# tap_analog_elavult.net
KiCad netlist of a schematic drawn in EAGLE
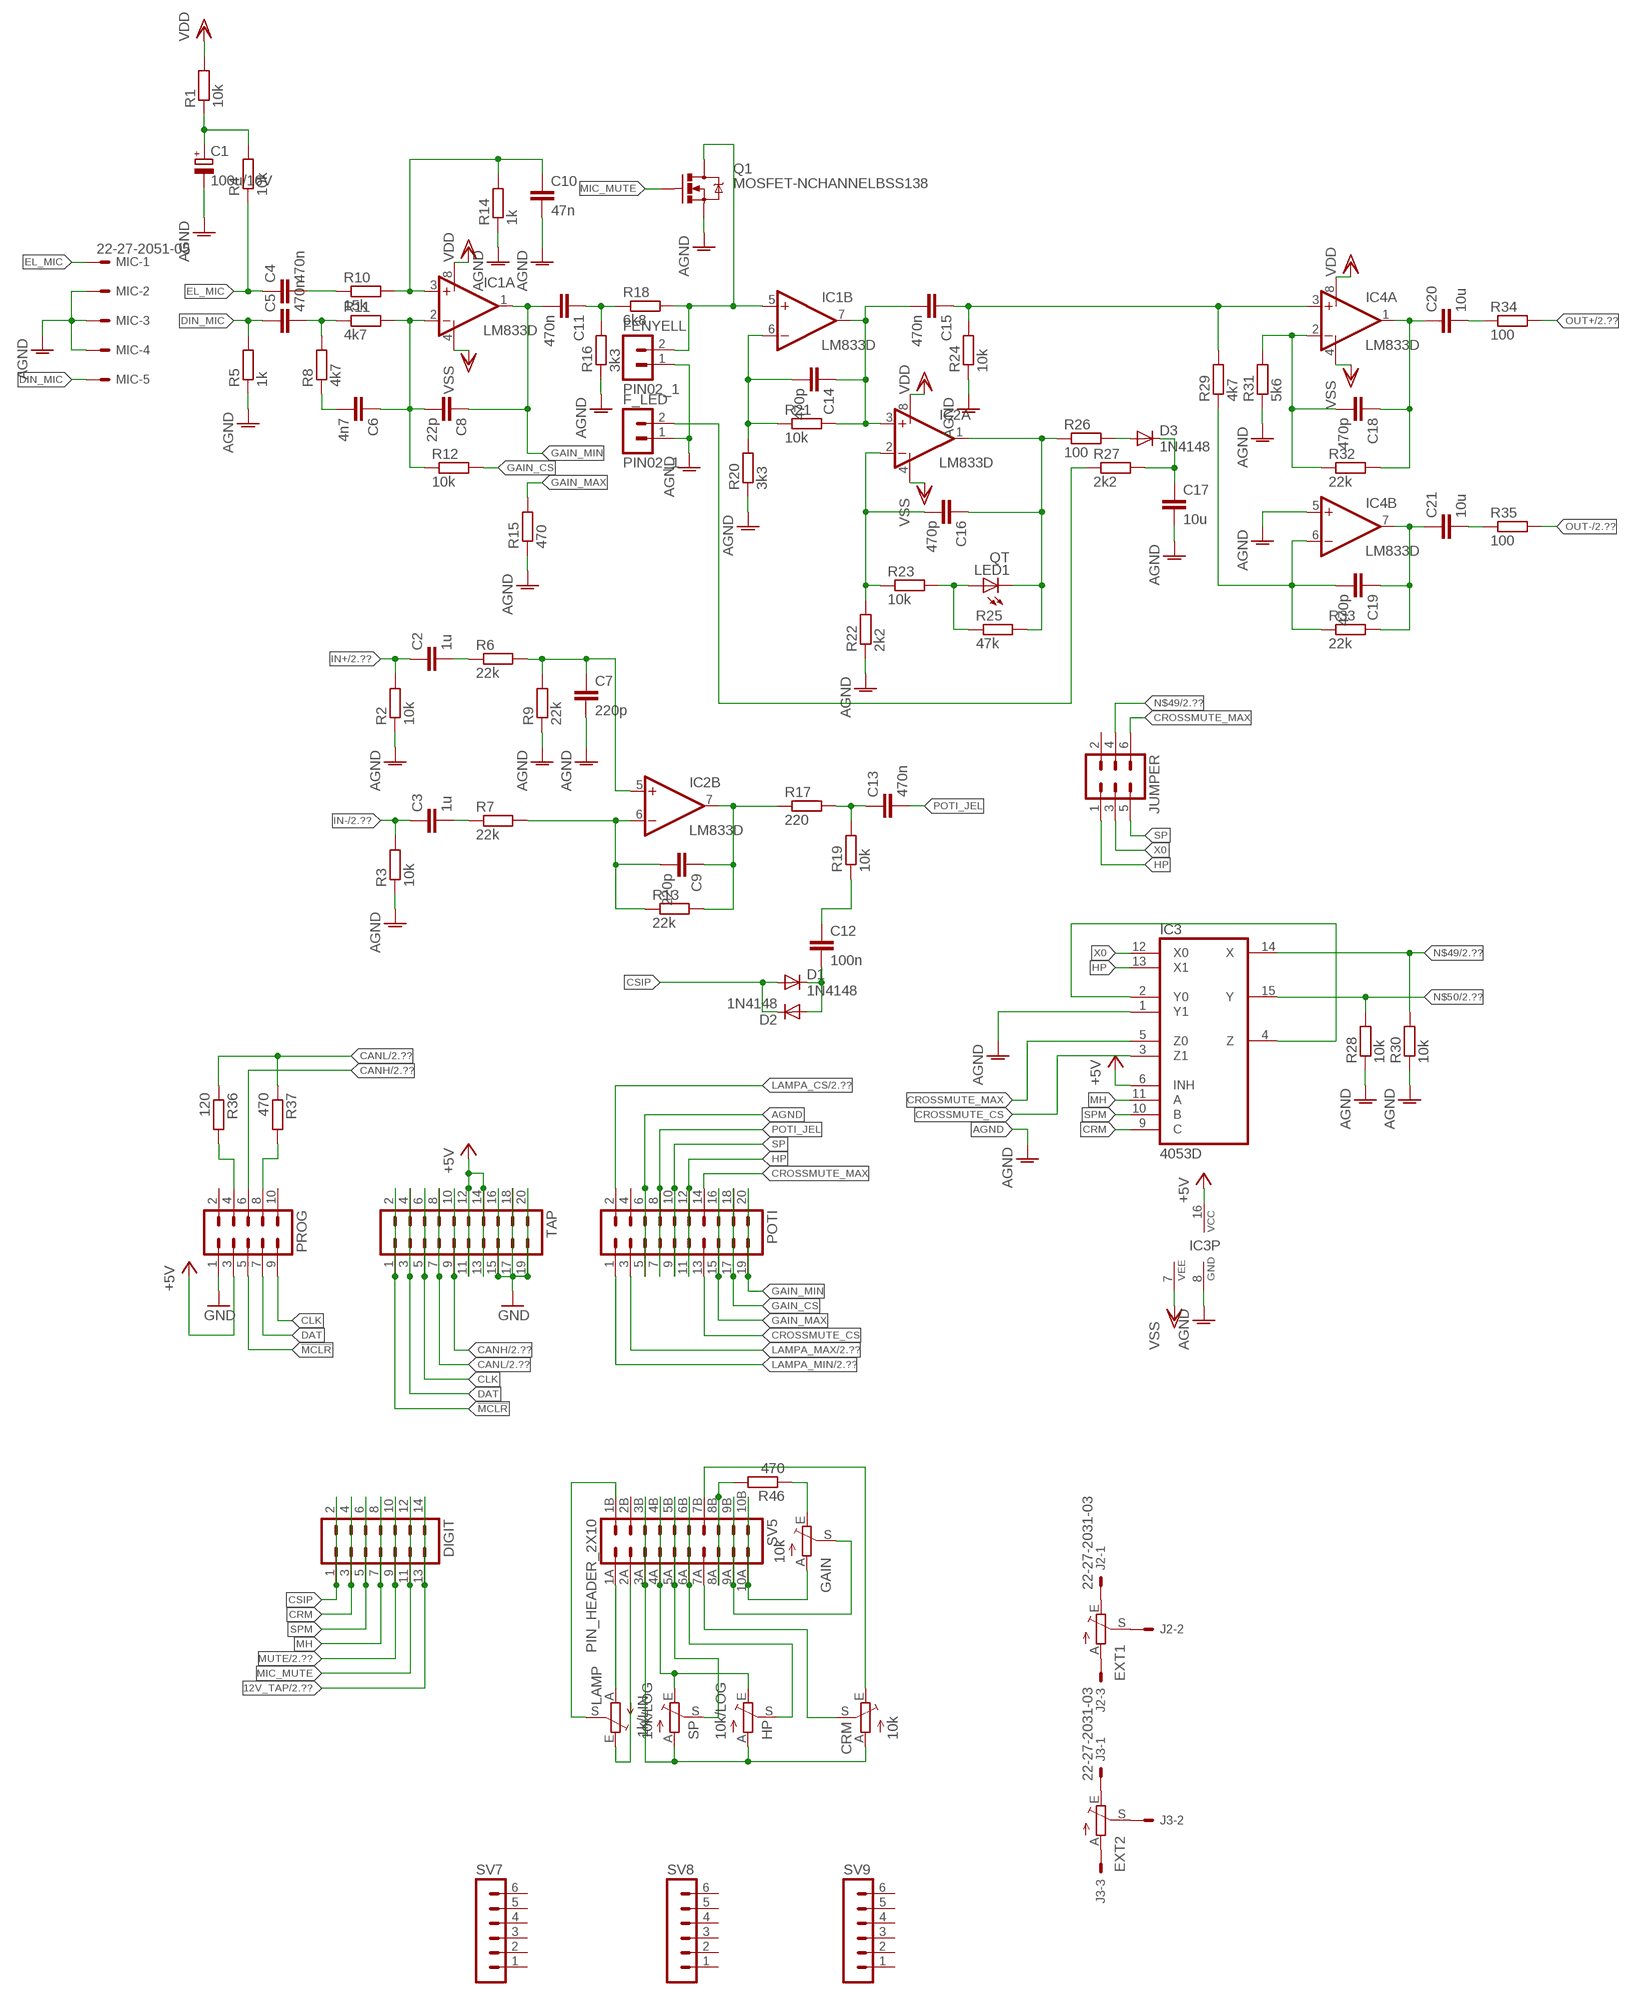
[diagram p0: schematic, sheet 1]
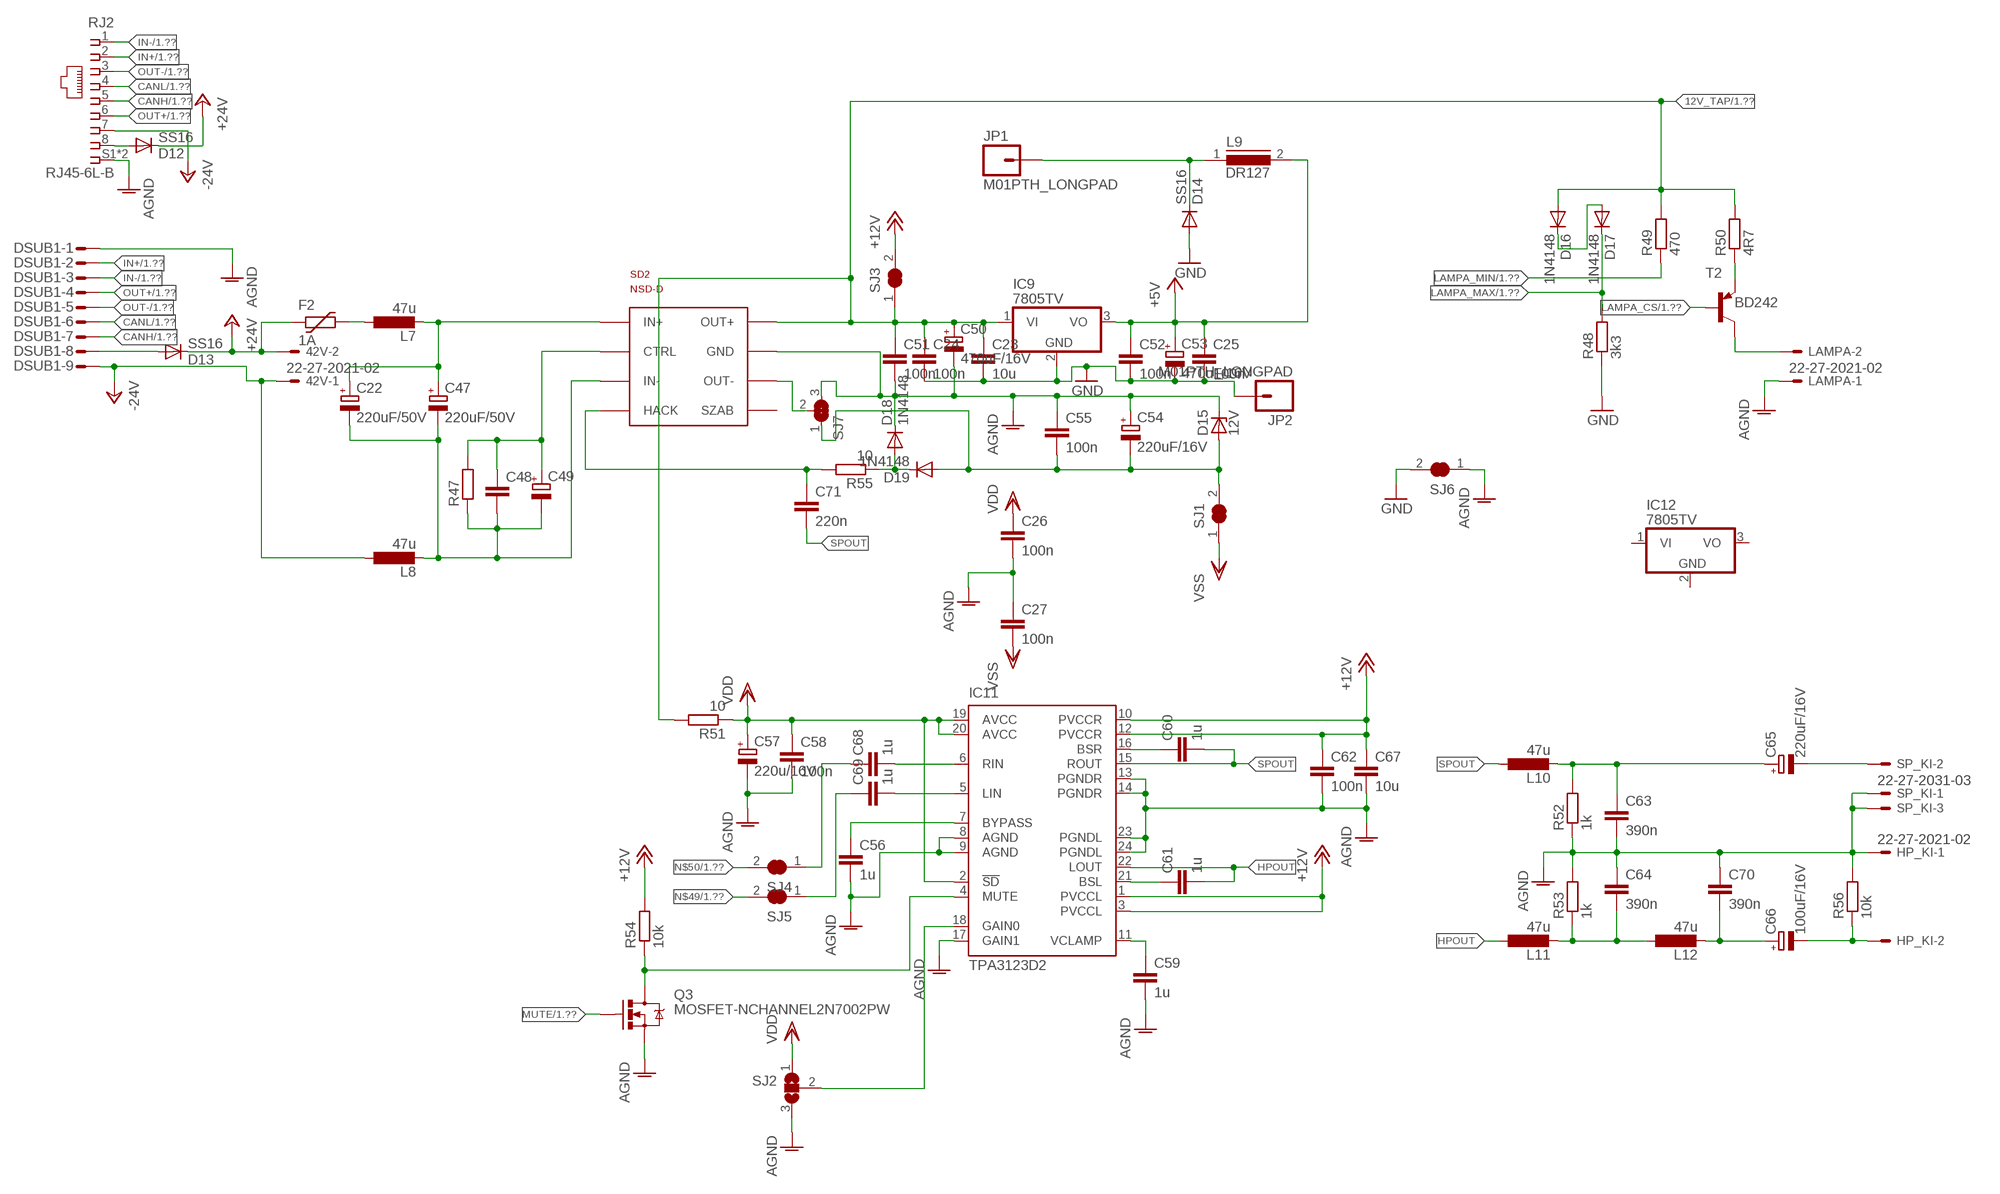
[diagram p1: schematic, sheet 2]

(export (version "E")
  (design (tool "Eeschema 10.0.6"))
  (components
    (comp (ref "42V")
      (value "22-27-2021-02")
      (footprint "eagle-import:6410-02")
      (libsource (lib "eagle-import") (part "22-?-0227-2021"))
    )
    (comp (ref "C22")
      (value "220uF/50V")
      (footprint "eagle-import:E3,5-8")
      (libsource (lib "eagle-import") (part "CPOL-EUE3.5-8"))
    )
    (comp (ref "C23")
      (value "10u")
      (footprint "eagle-import:C0805")
      (libsource (lib "eagle-import") (part "C-EUC0805"))
    )
    (comp (ref "C24")
      (value "100n")
      (footprint "eagle-import:C0805")
      (libsource (lib "eagle-import") (part "C-EUC0805"))
    )
    (comp (ref "C25")
      (value "100n")
      (footprint "eagle-import:C0805")
      (libsource (lib "eagle-import") (part "C-EUC0805"))
    )
    (comp (ref "C26")
      (value "100n")
      (footprint "eagle-import:C0805")
      (libsource (lib "eagle-import") (part "C-EUC0805"))
    )
    (comp (ref "C27")
      (value "100n")
      (footprint "eagle-import:C0805")
      (libsource (lib "eagle-import") (part "C-EUC0805"))
    )
    (comp (ref "C47")
      (value "220uF/50V")
      (footprint "eagle-import:E3,5-8")
      (libsource (lib "eagle-import") (part "CPOL-EUE3.5-8"))
    )
    (comp (ref "C48")
      (value "C-EUC0805")
      (footprint "eagle-import:C0805")
      (libsource (lib "eagle-import") (part "C-EUC0805"))
    )
    (comp (ref "C49")
      (value "CPOL-EUE2.5-5")
      (footprint "eagle-import:E2,5-5")
      (libsource (lib "eagle-import") (part "CPOL-EUE2.5-5"))
    )
    (comp (ref "C50")
      (value "470uF/16V")
      (footprint "eagle-import:E3,5-8")
      (libsource (lib "eagle-import") (part "CPOL-EUE3.5-8"))
    )
    (comp (ref "C51")
      (value "100n")
      (footprint "eagle-import:C0805")
      (libsource (lib "eagle-import") (part "C-EUC0805"))
    )
    (comp (ref "C52")
      (value "100n")
      (footprint "eagle-import:C0805")
      (libsource (lib "eagle-import") (part "C-EUC0805"))
    )
    (comp (ref "C53")
      (value "470uF/16V")
      (footprint "eagle-import:E3,5-8")
      (libsource (lib "eagle-import") (part "CPOL-EUE3.5-8"))
    )
    (comp (ref "C54")
      (value "220uF/16V")
      (footprint "eagle-import:E2,5-6")
      (libsource (lib "eagle-import") (part "CPOL-EUE2.5-6"))
    )
    (comp (ref "C55")
      (value "100n")
      (footprint "eagle-import:C0805")
      (libsource (lib "eagle-import") (part "C-EUC0805"))
    )
    (comp (ref "C56")
      (value "1u")
      (footprint "eagle-import:C0805")
      (libsource (lib "eagle-import") (part "C-EUC0805"))
    )
    (comp (ref "C57")
      (value "220u/16V")
      (footprint "eagle-import:E2,5-6")
      (libsource (lib "eagle-import") (part "CPOL-EUE2.5-6"))
    )
    (comp (ref "C58")
      (value "100n")
      (footprint "eagle-import:C0805")
      (libsource (lib "eagle-import") (part "C-EUC0805"))
    )
    (comp (ref "C59")
      (value "1u")
      (footprint "eagle-import:C0805")
      (libsource (lib "eagle-import") (part "C-EUC0805"))
    )
    (comp (ref "C60")
      (value "1u")
      (footprint "eagle-import:C0805")
      (libsource (lib "eagle-import") (part "C-EUC0805"))
    )
    (comp (ref "C61")
      (value "1u")
      (footprint "eagle-import:C0805")
      (libsource (lib "eagle-import") (part "C-EUC0805"))
    )
    (comp (ref "C62")
      (value "100n")
      (footprint "eagle-import:C0805")
      (libsource (lib "eagle-import") (part "C-EUC0805"))
    )
    (comp (ref "C63")
      (value "390n")
      (footprint "eagle-import:C0805")
      (libsource (lib "eagle-import") (part "C-EUC0805"))
    )
    (comp (ref "C64")
      (value "390n")
      (footprint "eagle-import:C0805")
      (libsource (lib "eagle-import") (part "C-EUC0805"))
    )
    (comp (ref "C65")
      (value "220uF/16V")
      (footprint "eagle-import:E2,5-6")
      (libsource (lib "eagle-import") (part "CPOL-EUE2.5-6"))
    )
    (comp (ref "C66")
      (value "100uF/16V")
      (footprint "eagle-import:E2,5-5")
      (libsource (lib "eagle-import") (part "CPOL-EUE2.5-5"))
    )
    (comp (ref "C67")
      (value "10u")
      (footprint "eagle-import:C0805")
      (libsource (lib "eagle-import") (part "C-EUC0805"))
    )
    (comp (ref "C68")
      (value "1u")
      (footprint "eagle-import:C0805")
      (libsource (lib "eagle-import") (part "C-EUC0805"))
    )
    (comp (ref "C69")
      (value "1u")
      (footprint "eagle-import:C0805")
      (libsource (lib "eagle-import") (part "C-EUC0805"))
    )
    (comp (ref "C70")
      (value "390n")
      (footprint "eagle-import:C0805")
      (libsource (lib "eagle-import") (part "C-EUC0805"))
    )
    (comp (ref "C71")
      (value "220n")
      (footprint "eagle-import:C0805")
      (libsource (lib "eagle-import") (part "C-EUC0805"))
    )
    (comp (ref "D12")
      (value "SS16")
      (footprint "eagle-import:DO-214AC")
      (libsource (lib "eagle-import") (part "dp_devices_DIODE-DO-214AC"))
    )
    (comp (ref "D13")
      (value "SS16")
      (footprint "eagle-import:DO-214AC")
      (libsource (lib "eagle-import") (part "dp_devices_DIODE-DO-214AC"))
    )
    (comp (ref "D14")
      (value "SS16")
      (footprint "eagle-import:DO-214AC")
      (libsource (lib "eagle-import") (part "dp_devices_DIODE-DO-214AC"))
    )
    (comp (ref "D15")
      (value "12V")
      (footprint "eagle-import:SOD80C")
      (libsource (lib "eagle-import") (part "ZENER-DIODESOD80C"))
    )
    (comp (ref "D16")
      (value "1N4148")
      (footprint "eagle-import:SOD80C")
      (libsource (lib "eagle-import") (part "DIODE-SOD80C"))
    )
    (comp (ref "D17")
      (value "1N4148")
      (footprint "eagle-import:SOD80C")
      (libsource (lib "eagle-import") (part "DIODE-SOD80C"))
    )
    (comp (ref "D18")
      (value "1N4148")
      (footprint "eagle-import:SOD80C")
      (libsource (lib "eagle-import") (part "DIODE-SOD80C"))
    )
    (comp (ref "D19")
      (value "1N4148")
      (footprint "eagle-import:SOD80C")
      (libsource (lib "eagle-import") (part "DIODE-SOD80C"))
    )
    (comp (ref "DSUB1")
      (value "M09-182S")
      (footprint "eagle-import:182-009-MALE")
      (libsource (lib "eagle-import") (part "M09?S-182"))
    )
    (comp (ref "F2")
      (value "1A")
      (footprint "eagle-import:PTC1812L")
      (libsource (lib "eagle-import") (part "FUSE_PTC-1812"))
    )
    (comp (ref "HP_KI")
      (value "22-27-2021-02")
      (footprint "eagle-import:6410-02")
      (libsource (lib "eagle-import") (part "22-?-0227-2021"))
    )
    (comp (ref "IC9")
      (value "7805TV")
      (footprint "eagle-import:TO220V")
      (libsource (lib "eagle-import") (part "78TV05"))
    )
    (comp (ref "IC11")
      (value "TPA3123D2")
      (footprint "eagle-import:PWP-TSSOP24")
      (fields (field (name "MPN") "TPA3123D2PWP"))
      (libsource (lib "eagle-import") (part "TPA3123D2"))
    )
    (comp (ref "IC12")
      (value "7805TV")
      (footprint "eagle-import:TO220V")
      (libsource (lib "eagle-import") (part "78TV05"))
    )
    (comp (ref "JP1")
      (value "M01PTH_LONGPAD")
      (footprint "eagle-import:1X01_LONGPAD")
      (libsource (lib "eagle-import") (part "M01PTH_LONGPAD"))
    )
    (comp (ref "JP2")
      (value "M01PTH_LONGPAD")
      (footprint "eagle-import:1X01_LONGPAD")
      (libsource (lib "eagle-import") (part "M01PTH_LONGPAD"))
    )
    (comp (ref "L7")
      (value "47u")
      (footprint "eagle-import:PIS2816")
      (libsource (lib "eagle-import") (part "L-EUPIS2816"))
    )
    (comp (ref "L8")
      (value "47u")
      (footprint "eagle-import:PIS2816")
      (libsource (lib "eagle-import") (part "L-EUPIS2816"))
    )
    (comp (ref "L9")
      (value "DR127")
      (footprint "eagle-import:DR127")
      (libsource (lib "eagle-import") (part "DR127"))
    )
    (comp (ref "L10")
      (value "47u")
      (footprint "eagle-import:PIS2816")
      (libsource (lib "eagle-import") (part "L-EUPIS2816"))
    )
    (comp (ref "L11")
      (value "47u")
      (footprint "eagle-import:PIS2816")
      (libsource (lib "eagle-import") (part "L-EUPIS2816"))
    )
    (comp (ref "L12")
      (value "47u")
      (footprint "eagle-import:PIS2816")
      (libsource (lib "eagle-import") (part "L-EUPIS2816"))
    )
    (comp (ref "LAMPA")
      (value "22-27-2021-02")
      (footprint "eagle-import:6410-02")
      (libsource (lib "eagle-import") (part "22-?-0227-2021"))
    )
    (comp (ref "Q3")
      (value "MOSFET-NCHANNEL2N7002PW")
      (footprint "eagle-import:SOT323")
      (libsource (lib "eagle-import") (part "MOSFET-NCHANNEL2N7002PW"))
    )
    (comp (ref "R47")
      (value "R-EU_R0805")
      (footprint "eagle-import:R0805")
      (libsource (lib "eagle-import") (part "R-EU_R0805"))
    )
    (comp (ref "R48")
      (value "3k3")
      (footprint "eagle-import:R0805")
      (libsource (lib "eagle-import") (part "R-EU_R0805"))
    )
    (comp (ref "R49")
      (value "470")
      (footprint "eagle-import:R0805")
      (libsource (lib "eagle-import") (part "R-EU_R0805"))
    )
    (comp (ref "R50")
      (value "4R7")
      (footprint "eagle-import:R0805")
      (libsource (lib "eagle-import") (part "R-EU_R0805"))
    )
    (comp (ref "R51")
      (value "10")
      (footprint "eagle-import:R1210")
      (libsource (lib "eagle-import") (part "R-EU_R1210"))
    )
    (comp (ref "R52")
      (value "1k")
      (footprint "eagle-import:R0805")
      (libsource (lib "eagle-import") (part "R-EU_R0805"))
    )
    (comp (ref "R53")
      (value "1k")
      (footprint "eagle-import:R0805")
      (libsource (lib "eagle-import") (part "R-EU_R0805"))
    )
    (comp (ref "R54")
      (value "10k")
      (footprint "eagle-import:R0805")
      (libsource (lib "eagle-import") (part "R-EU_R0805"))
    )
    (comp (ref "R55")
      (value "10")
      (footprint "eagle-import:R0805")
      (libsource (lib "eagle-import") (part "R-EU_R0805"))
    )
    (comp (ref "R56")
      (value "10k")
      (footprint "eagle-import:R0805")
      (libsource (lib "eagle-import") (part "R-EU_R0805"))
    )
    (comp (ref "RJ2")
      (value "RJ45-6L-B")
      (footprint "eagle-import:RJ45")
      (libsource (lib "eagle-import") (part "RJ45-6L-B"))
    )
    (comp (ref "SD2")
      (value "NSD-D")
      (footprint "eagle-import:NSD-D")
      (libsource (lib "eagle-import") (part "NSD-D"))
    )
    (comp (ref "SJ1")
      (value "SOLDERJUMPER_CLOSED")
      (footprint "eagle-import:SOLDERJUMPER_CLOSEDWIRE")
      (libsource (lib "eagle-import") (part "SOLDERJUMPER_CLOSED"))
    )
    (comp (ref "SJ2")
      (value "SJ2W")
      (footprint "eagle-import:SJ_2")
      (libsource (lib "eagle-import") (part "SJ2W"))
    )
    (comp (ref "SJ3")
      (value "SOLDERJUMPER_CLOSED")
      (footprint "eagle-import:SOLDERJUMPER_CLOSEDWIRE")
      (libsource (lib "eagle-import") (part "SOLDERJUMPER_CLOSED"))
    )
    (comp (ref "SJ4")
      (value "SOLDERJUMPER_CLOSED")
      (footprint "eagle-import:SOLDERJUMPER_CLOSEDWIRE")
      (libsource (lib "eagle-import") (part "SOLDERJUMPER_CLOSED"))
    )
    (comp (ref "SJ5")
      (value "SOLDERJUMPER_CLOSED")
      (footprint "eagle-import:SOLDERJUMPER_CLOSEDWIRE")
      (libsource (lib "eagle-import") (part "SOLDERJUMPER_CLOSED"))
    )
    (comp (ref "SJ6")
      (value "SOLDERJUMPER_CLOSED")
      (footprint "eagle-import:SOLDERJUMPER_CLOSEDWIRE")
      (libsource (lib "eagle-import") (part "SOLDERJUMPER_CLOSED"))
    )
    (comp (ref "SJ7")
      (value "SOLDERJUMPER_2WAY")
      (footprint "eagle-import:SOLDERJUMPER_2WAY_OPEN_NOPASTE")
      (libsource (lib "eagle-import") (part "SOLDERJUMPER_2WAY"))
    )
    (comp (ref "SP_KI")
      (value "22-27-2031-03")
      (footprint "eagle-import:6410-03")
      (libsource (lib "eagle-import") (part "22-?-0327-2031"))
    )
    (comp (ref "T2")
      (value "BD242")
      (footprint "eagle-import:TO220V")
      (libsource (lib "eagle-import") (part "-PNP-TO220V"))
    )
    (comp (ref "C1")
      (value "100u/16V")
      (footprint "eagle-import:E2,5-5")
      (libsource (lib "eagle-import") (part "CPOL-EUE2.5-5"))
    )
    (comp (ref "C2")
      (value "1u")
      (footprint "eagle-import:C0805")
      (libsource (lib "eagle-import") (part "C-EUC0805"))
    )
    (comp (ref "C3")
      (value "1u")
      (footprint "eagle-import:C0805")
      (libsource (lib "eagle-import") (part "C-EUC0805"))
    )
    (comp (ref "C4")
      (value "470n")
      (footprint "eagle-import:C0805")
      (libsource (lib "eagle-import") (part "C-EUC0805"))
    )
    (comp (ref "C5")
      (value "470n")
      (footprint "eagle-import:C0805")
      (libsource (lib "eagle-import") (part "C-EUC0805"))
    )
    (comp (ref "C6")
      (value "4n7")
      (footprint "eagle-import:C0805")
      (libsource (lib "eagle-import") (part "C-EUC0805"))
    )
    (comp (ref "C7")
      (value "220p")
      (footprint "eagle-import:C0805")
      (libsource (lib "eagle-import") (part "C-EUC0805"))
    )
    (comp (ref "C8")
      (value "22p")
      (footprint "eagle-import:C0805")
      (libsource (lib "eagle-import") (part "C-EUC0805"))
    )
    (comp (ref "C9")
      (value "220p")
      (footprint "eagle-import:C0805")
      (libsource (lib "eagle-import") (part "C-EUC0805"))
    )
    (comp (ref "C10")
      (value "47n")
      (footprint "eagle-import:C0805")
      (libsource (lib "eagle-import") (part "C-EUC0805"))
    )
    (comp (ref "C11")
      (value "470n")
      (footprint "eagle-import:C0805")
      (libsource (lib "eagle-import") (part "C-EUC0805"))
    )
    (comp (ref "C12")
      (value "100n")
      (footprint "eagle-import:C0805")
      (libsource (lib "eagle-import") (part "C-EUC0805"))
    )
    (comp (ref "C13")
      (value "470n")
      (footprint "eagle-import:C0805")
      (libsource (lib "eagle-import") (part "C-EUC0805"))
    )
    (comp (ref "C14")
      (value "470p")
      (footprint "eagle-import:C0805")
      (libsource (lib "eagle-import") (part "C-EUC0805"))
    )
    (comp (ref "C15")
      (value "470n")
      (footprint "eagle-import:C0805")
      (libsource (lib "eagle-import") (part "C-EUC0805"))
    )
    (comp (ref "C16")
      (value "470p")
      (footprint "eagle-import:C0805")
      (libsource (lib "eagle-import") (part "C-EUC0805"))
    )
    (comp (ref "C17")
      (value "10u")
      (footprint "eagle-import:C0805")
      (libsource (lib "eagle-import") (part "C-EUC0805"))
    )
    (comp (ref "C18")
      (value "470p")
      (footprint "eagle-import:C0805")
      (libsource (lib "eagle-import") (part "C-EUC0805"))
    )
    (comp (ref "C19")
      (value "470p")
      (footprint "eagle-import:C0805")
      (libsource (lib "eagle-import") (part "C-EUC0805"))
    )
    (comp (ref "C20")
      (value "10u")
      (footprint "eagle-import:C0805")
      (libsource (lib "eagle-import") (part "C-EUC0805"))
    )
    (comp (ref "C21")
      (value "10u")
      (footprint "eagle-import:C0805")
      (libsource (lib "eagle-import") (part "C-EUC0805"))
    )
    (comp (ref "CRM")
      (value "10k")
      (footprint "eagle-import:PT-10")
      (libsource (lib "eagle-import") (part "TRIM_EU-PT10"))
    )
    (comp (ref "D1")
      (value "1N4148")
      (footprint "eagle-import:SOD80C")
      (libsource (lib "eagle-import") (part "DIODE-SOD80C"))
    )
    (comp (ref "D2")
      (value "1N4148")
      (footprint "eagle-import:SOD80C")
      (libsource (lib "eagle-import") (part "DIODE-SOD80C"))
    )
    (comp (ref "D3")
      (value "1N4148")
      (footprint "eagle-import:SOD80C")
      (libsource (lib "eagle-import") (part "DIODE-SOD80C"))
    )
    (comp (ref "DIGIT")
      (value "MA07-2")
      (footprint "eagle-import:MA07-2")
      (libsource (lib "eagle-import") (part "MA07-2"))
    )
    (comp (ref "EXT1")
      (value "TRIM_EU-PT10")
      (footprint "eagle-import:PT-10")
      (libsource (lib "eagle-import") (part "TRIM_EU-PT10"))
    )
    (comp (ref "EXT2")
      (value "TRIM_EU-PT10")
      (footprint "eagle-import:PT-10")
      (libsource (lib "eagle-import") (part "TRIM_EU-PT10"))
    )
    (comp (ref "FENYELL")
      (value "PIN02_1")
      (footprint "eagle-import:PIN02_1")
      (libsource (lib "eagle-import") (part "PIN02_1"))
    )
    (comp (ref "F_LED")
      (value "PIN02_1")
      (footprint "eagle-import:PIN02_1")
      (libsource (lib "eagle-import") (part "PIN02_1"))
    )
    (comp (ref "GAIN")
      (value "10k")
      (footprint "eagle-import:PT-10")
      (libsource (lib "eagle-import") (part "TRIM_EU-PT10"))
    )
    (comp (ref "HP")
      (value "10k/LOG")
      (footprint "eagle-import:POT_NAR")
      (libsource (lib "eagle-import") (part "TRIM_EU-POT_WHOLE"))
    )
    (comp (ref "IC1")
      (value "LM833D")
      (footprint "eagle-import:SO08")
      (libsource (lib "eagle-import") (part "LM833D"))
    )
    (comp (ref "IC2")
      (value "LM833D")
      (footprint "eagle-import:SO08")
      (libsource (lib "eagle-import") (part "LM833D"))
    )
    (comp (ref "IC3")
      (value "4053D")
      (footprint "eagle-import:SO16")
      (libsource (lib "eagle-import") (part "4053D"))
    )
    (comp (ref "IC4")
      (value "LM833D")
      (footprint "eagle-import:SO08")
      (libsource (lib "eagle-import") (part "LM833D"))
    )
    (comp (ref "J2")
      (value "22-27-2031-03")
      (footprint "eagle-import:6410-03")
      (libsource (lib "eagle-import") (part "22-?-0327-2031"))
    )
    (comp (ref "J3")
      (value "22-27-2031-03")
      (footprint "eagle-import:6410-03")
      (libsource (lib "eagle-import") (part "22-?-0327-2031"))
    )
    (comp (ref "JUMPER")
      (value "MA03-2")
      (footprint "eagle-import:MA03-2")
      (libsource (lib "eagle-import") (part "MA03-2"))
    )
    (comp (ref "LAMP")
      (value "1k/LIN")
      (footprint "eagle-import:POT_NAR")
      (libsource (lib "eagle-import") (part "TRIM_EU-POT_WHOLE"))
    )
    (comp (ref "LED1")
      (value "QT")
      (footprint "eagle-import:LED3MM")
      (libsource (lib "eagle-import") (part "LED3MM"))
    )
    (comp (ref "MIC")
      (value "22-27-2051-05")
      (footprint "eagle-import:6410-05")
      (libsource (lib "eagle-import") (part "22-?-0527-2051"))
    )
    (comp (ref "POTI")
      (value "MA10-2")
      (footprint "eagle-import:MA10-2")
      (libsource (lib "eagle-import") (part "MA10-2"))
    )
    (comp (ref "PROG")
      (value "ML10L")
      (footprint "eagle-import:ML10L")
      (libsource (lib "eagle-import") (part "ML10L"))
    )
    (comp (ref "Q1")
      (value "MOSFET-NCHANNELBSS138")
      (footprint "eagle-import:SOT23")
      (libsource (lib "eagle-import") (part "MOSFET-NCHANNELBSS138"))
    )
    (comp (ref "R1")
      (value "10k")
      (footprint "eagle-import:R0805")
      (libsource (lib "eagle-import") (part "R-EU_R0805"))
    )
    (comp (ref "R2")
      (value "10k")
      (footprint "eagle-import:R0805")
      (libsource (lib "eagle-import") (part "R-EU_R0805"))
    )
    (comp (ref "R3")
      (value "10k")
      (footprint "eagle-import:R0805")
      (libsource (lib "eagle-import") (part "R-EU_R0805"))
    )
    (comp (ref "R4")
      (value "10k")
      (footprint "eagle-import:R0805")
      (libsource (lib "eagle-import") (part "R-EU_R0805"))
    )
    (comp (ref "R5")
      (value "1k")
      (footprint "eagle-import:R0805")
      (libsource (lib "eagle-import") (part "R-EU_R0805"))
    )
    (comp (ref "R6")
      (value "22k")
      (footprint "eagle-import:R0805")
      (libsource (lib "eagle-import") (part "R-EU_R0805"))
    )
    (comp (ref "R7")
      (value "22k")
      (footprint "eagle-import:R0805")
      (libsource (lib "eagle-import") (part "R-EU_R0805"))
    )
    (comp (ref "R8")
      (value "4k7")
      (footprint "eagle-import:R0805")
      (libsource (lib "eagle-import") (part "R-EU_R0805"))
    )
    (comp (ref "R9")
      (value "22k")
      (footprint "eagle-import:R0805")
      (libsource (lib "eagle-import") (part "R-EU_R0805"))
    )
    (comp (ref "R10")
      (value "15k")
      (footprint "eagle-import:R0805")
      (libsource (lib "eagle-import") (part "R-EU_R0805"))
    )
    (comp (ref "R11")
      (value "4k7")
      (footprint "eagle-import:R0805")
      (libsource (lib "eagle-import") (part "R-EU_R0805"))
    )
    (comp (ref "R12")
      (value "10k")
      (footprint "eagle-import:R0805")
      (libsource (lib "eagle-import") (part "R-EU_R0805"))
    )
    (comp (ref "R13")
      (value "22k")
      (footprint "eagle-import:R0805")
      (libsource (lib "eagle-import") (part "R-EU_R0805"))
    )
    (comp (ref "R14")
      (value "1k")
      (footprint "eagle-import:R0805")
      (libsource (lib "eagle-import") (part "R-EU_R0805"))
    )
    (comp (ref "R15")
      (value "470")
      (footprint "eagle-import:R0805")
      (libsource (lib "eagle-import") (part "R-EU_R0805"))
    )
    (comp (ref "R16")
      (value "3k3")
      (footprint "eagle-import:R0805")
      (libsource (lib "eagle-import") (part "R-EU_R0805"))
    )
    (comp (ref "R17")
      (value "220")
      (footprint "eagle-import:R0805")
      (libsource (lib "eagle-import") (part "R-EU_R0805"))
    )
    (comp (ref "R18")
      (value "6k8")
      (footprint "eagle-import:R0805")
      (libsource (lib "eagle-import") (part "R-EU_R0805"))
    )
    (comp (ref "R19")
      (value "10k")
      (footprint "eagle-import:R0805")
      (libsource (lib "eagle-import") (part "R-EU_R0805"))
    )
    (comp (ref "R20")
      (value "3k3")
      (footprint "eagle-import:R0805")
      (libsource (lib "eagle-import") (part "R-EU_R0805"))
    )
    (comp (ref "R21")
      (value "10k")
      (footprint "eagle-import:R0805")
      (libsource (lib "eagle-import") (part "R-EU_R0805"))
    )
    (comp (ref "R22")
      (value "2k2")
      (footprint "eagle-import:R0805")
      (libsource (lib "eagle-import") (part "R-EU_R0805"))
    )
    (comp (ref "R23")
      (value "10k")
      (footprint "eagle-import:R0805")
      (libsource (lib "eagle-import") (part "R-EU_R0805"))
    )
    (comp (ref "R24")
      (value "10k")
      (footprint "eagle-import:R0805")
      (libsource (lib "eagle-import") (part "R-EU_R0805"))
    )
    (comp (ref "R25")
      (value "47k")
      (footprint "eagle-import:R0805")
      (libsource (lib "eagle-import") (part "R-EU_R0805"))
    )
    (comp (ref "R26")
      (value "100")
      (footprint "eagle-import:R0805")
      (libsource (lib "eagle-import") (part "R-EU_R0805"))
    )
    (comp (ref "R27")
      (value "2k2")
      (footprint "eagle-import:R0805")
      (libsource (lib "eagle-import") (part "R-EU_R0805"))
    )
    (comp (ref "R28")
      (value "10k")
      (footprint "eagle-import:R0805")
      (libsource (lib "eagle-import") (part "R-EU_R0805"))
    )
    (comp (ref "R29")
      (value "4k7")
      (footprint "eagle-import:R0805")
      (libsource (lib "eagle-import") (part "R-EU_R0805"))
    )
    (comp (ref "R30")
      (value "10k")
      (footprint "eagle-import:R0805")
      (libsource (lib "eagle-import") (part "R-EU_R0805"))
    )
    (comp (ref "R31")
      (value "5k6")
      (footprint "eagle-import:R0805")
      (libsource (lib "eagle-import") (part "R-EU_R0805"))
    )
    (comp (ref "R32")
      (value "22k")
      (footprint "eagle-import:R0805")
      (libsource (lib "eagle-import") (part "R-EU_R0805"))
    )
    (comp (ref "R33")
      (value "22k")
      (footprint "eagle-import:R0805")
      (libsource (lib "eagle-import") (part "R-EU_R0805"))
    )
    (comp (ref "R34")
      (value "100")
      (footprint "eagle-import:R0805")
      (libsource (lib "eagle-import") (part "R-EU_R0805"))
    )
    (comp (ref "R35")
      (value "100")
      (footprint "eagle-import:R0805")
      (libsource (lib "eagle-import") (part "R-EU_R0805"))
    )
    (comp (ref "R36")
      (value "120")
      (footprint "eagle-import:R0805")
      (libsource (lib "eagle-import") (part "R-EU_R0805"))
    )
    (comp (ref "R37")
      (value "470")
      (footprint "eagle-import:R0805")
      (libsource (lib "eagle-import") (part "R-EU_R0805"))
    )
    (comp (ref "R46")
      (value "470")
      (footprint "eagle-import:R0805")
      (libsource (lib "eagle-import") (part "R-EU_R0805"))
    )
    (comp (ref "SP")
      (value "10k/LOG")
      (footprint "eagle-import:POT_NAR")
      (libsource (lib "eagle-import") (part "TRIM_EU-POT_WHOLE"))
    )
    (comp (ref "SV5")
      (value "PIN_HEADER_2X10")
      (footprint "eagle-import:PIN_HEADER_2X10SMD")
      (libsource (lib "eagle-import") (part "PIN_HEADER_2X10"))
    )
    (comp (ref "SV7")
      (value "MA06-1")
      (footprint "eagle-import:MA06-1")
      (libsource (lib "eagle-import") (part "MA06-1"))
    )
    (comp (ref "SV8")
      (value "MA06-1")
      (footprint "eagle-import:MA06-1")
      (libsource (lib "eagle-import") (part "MA06-1"))
    )
    (comp (ref "SV9")
      (value "MA06-1")
      (footprint "eagle-import:MA06-1")
      (libsource (lib "eagle-import") (part "MA06-1"))
    )
    (comp (ref "TAP")
      (value "MA10-2")
      (footprint "eagle-import:MA10-2")
      (libsource (lib "eagle-import") (part "MA10-2"))
    )
  )
  (nets
    (net (code "1") (name "+5V") (class "Default")
      (node (ref "C25") (pin "1") (pinfunction "1_1") (pintype "passive"))
      (node (ref "C52") (pin "1") (pinfunction "1_1") (pintype "passive"))
      (node (ref "C53") (pin "+") (pinfunction "+_+") (pintype "passive"))
      (node (ref "IC3") (pin "16") (pinfunction "VCC_16") (pintype "power_in"))
      (node (ref "IC3") (pin "6") (pinfunction "INH_6") (pintype "input"))
      (node (ref "IC9") (pin "3") (pinfunction "VO_3") (pintype "passive"))
      (node (ref "L9") (pin "2") (pinfunction "2_2") (pintype "passive"))
      (node (ref "PROG") (pin "3") (pinfunction "3_3") (pintype "passive"))
      (node (ref "TAP") (pin "11") (pinfunction "11_11") (pintype "passive"))
      (node (ref "TAP") (pin "12") (pinfunction "12_12") (pintype "passive"))
      (node (ref "TAP") (pin "13") (pinfunction "13_13") (pintype "passive"))
      (node (ref "TAP") (pin "14") (pinfunction "14_14") (pintype "passive"))
    )
    (net (code "2") (name "+12V") (class "Default")
      (node (ref "C62") (pin "1") (pinfunction "1_1") (pintype "passive"))
      (node (ref "C67") (pin "1") (pinfunction "1_1") (pintype "passive"))
      (node (ref "IC11") (pin "1") (pinfunction "PVCCL_1") (pintype "input"))
      (node (ref "IC11") (pin "10") (pinfunction "PVCCR_10") (pintype "input"))
      (node (ref "IC11") (pin "12") (pinfunction "PVCCR_12") (pintype "input"))
      (node (ref "IC11") (pin "3") (pinfunction "PVCCL_3") (pintype "input"))
      (node (ref "R54") (pin "2") (pinfunction "2_2") (pintype "passive"))
      (node (ref "SJ3") (pin "2") (pinfunction "2_2") (pintype "passive"))
    )
    (net (code "3") (name "+24V") (class "Default")
      (node (ref "42V") (pin "2") (pinfunction "S_2") (pintype "passive"))
      (node (ref "D12") (pin "1") (pinfunction "C_1") (pintype "passive"))
      (node (ref "D13") (pin "1") (pinfunction "C_1") (pintype "passive"))
      (node (ref "F2") (pin "1") (pinfunction "1_1") (pintype "passive"))
    )
    (net (code "4") (name "-24V") (class "Default")
      (node (ref "42V") (pin "1") (pinfunction "S_1") (pintype "passive"))
      (node (ref "DSUB1") (pin "9") (pinfunction "M_9") (pintype "passive"))
      (node (ref "L8") (pin "1") (pinfunction "1_1") (pintype "passive"))
      (node (ref "RJ2") (pin "7") (pinfunction "7_7") (pintype "passive"))
    )
    (net (code "5") (name "12V_TAP") (class "Default")
      (node (ref "C23") (pin "1") (pinfunction "1_1") (pintype "passive"))
      (node (ref "C24") (pin "1") (pinfunction "1_1") (pintype "passive"))
      (node (ref "C50") (pin "+") (pinfunction "+_+") (pintype "passive"))
      (node (ref "C51") (pin "1") (pinfunction "1_1") (pintype "passive"))
      (node (ref "D16") (pin "A") (pinfunction "A_A") (pintype "passive"))
      (node (ref "DIGIT") (pin "13") (pinfunction "13_13") (pintype "passive"))
      (node (ref "DIGIT") (pin "14") (pinfunction "14_14") (pintype "passive"))
      (node (ref "IC9") (pin "1") (pinfunction "VI_1") (pintype "input"))
      (node (ref "R49") (pin "2") (pinfunction "2_2") (pintype "passive"))
      (node (ref "R50") (pin "2") (pinfunction "2_2") (pintype "passive"))
      (node (ref "R51") (pin "2") (pinfunction "2_2") (pintype "passive"))
      (node (ref "SD2") (pin "OUT+") (pinfunction "OUT+_OUT+") (pintype "bidirectional"))
      (node (ref "SJ3") (pin "1") (pinfunction "1_1") (pintype "passive"))
    )
    (net (code "6") (name "AGND") (class "Default")
      (node (ref "C1") (pin "-") (pinfunction "-_-") (pintype "passive"))
      (node (ref "C10") (pin "2") (pinfunction "2_2") (pintype "passive"))
      (node (ref "C17") (pin "2") (pinfunction "2_2") (pintype "passive"))
      (node (ref "C26") (pin "2") (pinfunction "2_2") (pintype "passive"))
      (node (ref "C27") (pin "1") (pinfunction "1_1") (pintype "passive"))
      (node (ref "C50") (pin "-") (pinfunction "-_-") (pintype "passive"))
      (node (ref "C51") (pin "2") (pinfunction "2_2") (pintype "passive"))
      (node (ref "C54") (pin "+") (pinfunction "+_+") (pintype "passive"))
      (node (ref "C55") (pin "1") (pinfunction "1_1") (pintype "passive"))
      (node (ref "C56") (pin "2") (pinfunction "2_2") (pintype "passive"))
      (node (ref "C57") (pin "-") (pinfunction "-_-") (pintype "passive"))
      (node (ref "C58") (pin "2") (pinfunction "2_2") (pintype "passive"))
      (node (ref "C59") (pin "2") (pinfunction "2_2") (pintype "passive"))
      (node (ref "C62") (pin "2") (pinfunction "2_2") (pintype "passive"))
      (node (ref "C63") (pin "2") (pinfunction "2_2") (pintype "passive"))
      (node (ref "C64") (pin "1") (pinfunction "1_1") (pintype "passive"))
      (node (ref "C67") (pin "2") (pinfunction "2_2") (pintype "passive"))
      (node (ref "C7") (pin "2") (pinfunction "2_2") (pintype "passive"))
      (node (ref "C70") (pin "1") (pinfunction "1_1") (pintype "passive"))
      (node (ref "D15") (pin "C") (pinfunction "C_C") (pintype "passive"))
      (node (ref "D18") (pin "C") (pinfunction "C_C") (pintype "passive"))
      (node (ref "DSUB1") (pin "1") (pinfunction "M_1") (pintype "passive"))
      (node (ref "FENYELL") (pin "1") (pinfunction "1_1") (pintype "passive"))
      (node (ref "F_LED") (pin "1") (pinfunction "1_1") (pintype "passive"))
      (node (ref "HP_KI") (pin "1") (pinfunction "S_1") (pintype "passive"))
      (node (ref "IC11") (pin "13") (pinfunction "PGNDR_13") (pintype "input"))
      (node (ref "IC11") (pin "14") (pinfunction "PGNDR_14") (pintype "input"))
      (node (ref "IC11") (pin "17") (pinfunction "GAIN1_17") (pintype "input"))
      (node (ref "IC11") (pin "23") (pinfunction "PGNDL_23") (pintype "input"))
      (node (ref "IC11") (pin "24") (pinfunction "PGNDL_24") (pintype "input"))
      (node (ref "IC11") (pin "8") (pinfunction "AGND_8") (pintype "input"))
      (node (ref "IC11") (pin "9") (pinfunction "AGND_9") (pintype "input"))
      (node (ref "IC3") (pin "1") (pinfunction "Y1_1") (pintype "bidirectional"))
      (node (ref "IC3") (pin "8") (pinfunction "GND_8") (pintype "power_in"))
      (node (ref "IC4") (pin "5") (pinfunction "+IN_5") (pintype "input"))
      (node (ref "LAMPA") (pin "1") (pinfunction "S_1") (pintype "passive"))
      (node (ref "MIC") (pin "2") (pinfunction "S_2") (pintype "passive"))
      (node (ref "MIC") (pin "3") (pinfunction "S_3") (pintype "passive"))
      (node (ref "MIC") (pin "4") (pinfunction "S_4") (pintype "passive"))
      (node (ref "POTI") (pin "5") (pinfunction "5_5") (pintype "passive"))
      (node (ref "POTI") (pin "6") (pinfunction "6_6") (pintype "passive"))
      (node (ref "Q1") (pin "2") (pinfunction "S_2") (pintype "passive"))
      (node (ref "Q3") (pin "2") (pinfunction "S_2") (pintype "passive"))
      (node (ref "R14") (pin "1") (pinfunction "1_1") (pintype "passive"))
      (node (ref "R15") (pin "1") (pinfunction "1_1") (pintype "passive"))
      (node (ref "R16") (pin "1") (pinfunction "1_1") (pintype "passive"))
      (node (ref "R2") (pin "1") (pinfunction "1_1") (pintype "passive"))
      (node (ref "R20") (pin "1") (pinfunction "1_1") (pintype "passive"))
      (node (ref "R22") (pin "1") (pinfunction "1_1") (pintype "passive"))
      (node (ref "R24") (pin "1") (pinfunction "1_1") (pintype "passive"))
      (node (ref "R28") (pin "1") (pinfunction "1_1") (pintype "passive"))
      (node (ref "R3") (pin "1") (pinfunction "1_1") (pintype "passive"))
      (node (ref "R30") (pin "1") (pinfunction "1_1") (pintype "passive"))
      (node (ref "R31") (pin "1") (pinfunction "1_1") (pintype "passive"))
      (node (ref "R5") (pin "1") (pinfunction "1_1") (pintype "passive"))
      (node (ref "R52") (pin "1") (pinfunction "1_1") (pintype "passive"))
      (node (ref "R53") (pin "2") (pinfunction "2_2") (pintype "passive"))
      (node (ref "R56") (pin "2") (pinfunction "2_2") (pintype "passive"))
      (node (ref "R9") (pin "1") (pinfunction "1_1") (pintype "passive"))
      (node (ref "RJ2") (pin "S1") (pinfunction "S_S1") (pintype "passive"))
      (node (ref "RJ2") (pin "S2") (pinfunction "S_S2") (pintype "passive"))
      (node (ref "SD2") (pin "COMMON") (pinfunction "GND_COMMON") (pintype "bidirectional"))
      (node (ref "SJ2") (pin "3") (pinfunction "3_3") (pintype "passive"))
      (node (ref "SJ6") (pin "1") (pinfunction "1_1") (pintype "passive"))
      (node (ref "SJ7") (pin "3") (pinfunction "3_3") (pintype "passive"))
      (node (ref "SP_KI") (pin "1") (pinfunction "S_1") (pintype "passive"))
      (node (ref "SP_KI") (pin "3") (pinfunction "S_3") (pintype "passive"))
    )
    (net (code "7") (name "CANH") (class "Default")
      (node (ref "DSUB1") (pin "7") (pinfunction "M_7") (pintype "passive"))
      (node (ref "PROG") (pin "6") (pinfunction "6_6") (pintype "passive"))
      (node (ref "RJ2") (pin "5") (pinfunction "5_5") (pintype "passive"))
      (node (ref "TAP") (pin "10") (pinfunction "10_10") (pintype "passive"))
      (node (ref "TAP") (pin "9") (pinfunction "9_9") (pintype "passive"))
    )
    (net (code "8") (name "CANL") (class "Default")
      (node (ref "DSUB1") (pin "6") (pinfunction "M_6") (pintype "passive"))
      (node (ref "R36") (pin "1") (pinfunction "1_1") (pintype "passive"))
      (node (ref "R37") (pin "1") (pinfunction "1_1") (pintype "passive"))
      (node (ref "RJ2") (pin "4") (pinfunction "4_4") (pintype "passive"))
      (node (ref "TAP") (pin "7") (pinfunction "7_7") (pintype "passive"))
      (node (ref "TAP") (pin "8") (pinfunction "8_8") (pintype "passive"))
    )
    (net (code "9") (name "CLK") (class "Default")
      (node (ref "PROG") (pin "9") (pinfunction "9_9") (pintype "passive"))
      (node (ref "TAP") (pin "5") (pinfunction "5_5") (pintype "passive"))
      (node (ref "TAP") (pin "6") (pinfunction "6_6") (pintype "passive"))
    )
    (net (code "10") (name "CRM") (class "Default")
      (node (ref "DIGIT") (pin "3") (pinfunction "3_3") (pintype "passive"))
      (node (ref "DIGIT") (pin "4") (pinfunction "4_4") (pintype "passive"))
      (node (ref "IC3") (pin "9") (pinfunction "C_9") (pintype "input"))
    )
    (net (code "11") (name "CROSSMUTE_CS") (class "Default")
      (node (ref "IC3") (pin "3") (pinfunction "Z1_3") (pintype "bidirectional"))
      (node (ref "POTI") (pin "13") (pinfunction "13_13") (pintype "passive"))
    )
    (net (code "12") (name "CROSSMUTE_MAX") (class "Default")
      (node (ref "IC3") (pin "5") (pinfunction "Z0_5") (pintype "bidirectional"))
      (node (ref "JUMPER") (pin "6") (pinfunction "6_6") (pintype "passive"))
      (node (ref "POTI") (pin "14") (pinfunction "14_14") (pintype "passive"))
    )
    (net (code "13") (name "CSIP") (class "Default")
      (node (ref "D1") (pin "A") (pinfunction "A_A") (pintype "passive"))
      (node (ref "D2") (pin "C") (pinfunction "C_C") (pintype "passive"))
      (node (ref "DIGIT") (pin "1") (pinfunction "1_1") (pintype "passive"))
      (node (ref "DIGIT") (pin "2") (pinfunction "2_2") (pintype "passive"))
    )
    (net (code "14") (name "DAT") (class "Default")
      (node (ref "PROG") (pin "7") (pinfunction "7_7") (pintype "passive"))
      (node (ref "TAP") (pin "3") (pinfunction "3_3") (pintype "passive"))
      (node (ref "TAP") (pin "4") (pinfunction "4_4") (pintype "passive"))
    )
    (net (code "15") (name "DIN_MIC") (class "Default")
      (node (ref "C5") (pin "1") (pinfunction "1_1") (pintype "passive"))
      (node (ref "MIC") (pin "5") (pinfunction "S_5") (pintype "passive"))
      (node (ref "R5") (pin "2") (pinfunction "2_2") (pintype "passive"))
    )
    (net (code "16") (name "EL_MIC") (class "Default")
      (node (ref "C4") (pin "1") (pinfunction "1_1") (pintype "passive"))
      (node (ref "MIC") (pin "1") (pinfunction "S_1") (pintype "passive"))
      (node (ref "R4") (pin "1") (pinfunction "1_1") (pintype "passive"))
    )
    (net (code "17") (name "GAIN_CS") (class "Default")
      (node (ref "POTI") (pin "17") (pinfunction "17_17") (pintype "passive"))
      (node (ref "POTI") (pin "18") (pinfunction "18_18") (pintype "passive"))
      (node (ref "R12") (pin "2") (pinfunction "2_2") (pintype "passive"))
    )
    (net (code "18") (name "GAIN_MAX") (class "Default")
      (node (ref "POTI") (pin "15") (pinfunction "15_15") (pintype "passive"))
      (node (ref "POTI") (pin "16") (pinfunction "16_16") (pintype "passive"))
      (node (ref "R15") (pin "2") (pinfunction "2_2") (pintype "passive"))
    )
    (net (code "19") (name "GAIN_MIN") (class "Default")
      (node (ref "C11") (pin "2") (pinfunction "2_2") (pintype "passive"))
      (node (ref "C8") (pin "1") (pinfunction "1_1") (pintype "passive"))
      (node (ref "IC1") (pin "1") (pinfunction "OUT_1") (pintype "output"))
      (node (ref "POTI") (pin "19") (pinfunction "19_19") (pintype "passive"))
      (node (ref "POTI") (pin "20") (pinfunction "20_20") (pintype "passive"))
    )
    (net (code "20") (name "GND") (class "Default")
      (node (ref "C23") (pin "2") (pinfunction "2_2") (pintype "passive"))
      (node (ref "C24") (pin "2") (pinfunction "2_2") (pintype "passive"))
      (node (ref "C25") (pin "2") (pinfunction "2_2") (pintype "passive"))
      (node (ref "C52") (pin "2") (pinfunction "2_2") (pintype "passive"))
      (node (ref "C53") (pin "-") (pinfunction "-_-") (pintype "passive"))
      (node (ref "D14") (pin "2") (pinfunction "A_2") (pintype "passive"))
      (node (ref "IC9") (pin "2") (pinfunction "GND_2") (pintype "passive"))
      (node (ref "JP2") (pin "1") (pinfunction "1_1") (pintype "passive"))
      (node (ref "PROG") (pin "1") (pinfunction "1_1") (pintype "passive"))
      (node (ref "R48") (pin "1") (pinfunction "1_1") (pintype "passive"))
      (node (ref "SJ6") (pin "2") (pinfunction "2_2") (pintype "passive"))
      (node (ref "TAP") (pin "15") (pinfunction "15_15") (pintype "passive"))
      (node (ref "TAP") (pin "16") (pinfunction "16_16") (pintype "passive"))
      (node (ref "TAP") (pin "17") (pinfunction "17_17") (pintype "passive"))
      (node (ref "TAP") (pin "18") (pinfunction "18_18") (pintype "passive"))
      (node (ref "TAP") (pin "19") (pinfunction "19_19") (pintype "passive"))
      (node (ref "TAP") (pin "20") (pinfunction "20_20") (pintype "passive"))
    )
    (net (code "21") (name "HP") (class "Default")
      (node (ref "IC3") (pin "13") (pinfunction "X1_13") (pintype "bidirectional"))
      (node (ref "JUMPER") (pin "1") (pinfunction "1_1") (pintype "passive"))
      (node (ref "POTI") (pin "11") (pinfunction "11_11") (pintype "passive"))
      (node (ref "POTI") (pin "12") (pinfunction "12_12") (pintype "passive"))
    )
    (net (code "22") (name "HPOUT") (class "Default")
      (node (ref "C61") (pin "2") (pinfunction "2_2") (pintype "passive"))
      (node (ref "IC11") (pin "22") (pinfunction "LOUT_22") (pintype "output"))
      (node (ref "L11") (pin "1") (pinfunction "1_1") (pintype "passive"))
    )
    (net (code "23") (name "IN+") (class "Default")
      (node (ref "C2") (pin "1") (pinfunction "1_1") (pintype "passive"))
      (node (ref "DSUB1") (pin "2") (pinfunction "M_2") (pintype "passive"))
      (node (ref "R2") (pin "2") (pinfunction "2_2") (pintype "passive"))
      (node (ref "RJ2") (pin "2") (pinfunction "2_2") (pintype "passive"))
    )
    (net (code "24") (name "IN-") (class "Default")
      (node (ref "C3") (pin "1") (pinfunction "1_1") (pintype "passive"))
      (node (ref "DSUB1") (pin "3") (pinfunction "M_3") (pintype "passive"))
      (node (ref "R3") (pin "2") (pinfunction "2_2") (pintype "passive"))
      (node (ref "RJ2") (pin "1") (pinfunction "1_1") (pintype "passive"))
    )
    (net (code "25") (name "LAMPA_CS") (class "Default")
      (node (ref "POTI") (pin "2") (pinfunction "2_2") (pintype "passive"))
      (node (ref "T2") (pin "1") (pinfunction "B_1") (pintype "passive"))
    )
    (net (code "26") (name "LAMPA_MAX") (class "Default")
      (node (ref "D17") (pin "C") (pinfunction "C_C") (pintype "passive"))
      (node (ref "POTI") (pin "3") (pinfunction "3_3") (pintype "passive"))
      (node (ref "R48") (pin "2") (pinfunction "2_2") (pintype "passive"))
    )
    (net (code "27") (name "LAMPA_MIN") (class "Default")
      (node (ref "POTI") (pin "1") (pinfunction "1_1") (pintype "passive"))
      (node (ref "R49") (pin "1") (pinfunction "1_1") (pintype "passive"))
    )
    (net (code "28") (name "MH") (class "Default")
      (node (ref "DIGIT") (pin "7") (pinfunction "7_7") (pintype "passive"))
      (node (ref "DIGIT") (pin "8") (pinfunction "8_8") (pintype "passive"))
      (node (ref "IC3") (pin "11") (pinfunction "A_11") (pintype "input"))
    )
    (net (code "29") (name "MIC_MUTE") (class "Default")
      (node (ref "DIGIT") (pin "11") (pinfunction "11_11") (pintype "passive"))
      (node (ref "DIGIT") (pin "12") (pinfunction "12_12") (pintype "passive"))
      (node (ref "Q1") (pin "1") (pinfunction "G_1") (pintype "passive"))
    )
    (net (code "30") (name "MUTE") (class "Default")
      (node (ref "DIGIT") (pin "10") (pinfunction "10_10") (pintype "passive"))
      (node (ref "DIGIT") (pin "9") (pinfunction "9_9") (pintype "passive"))
      (node (ref "Q3") (pin "1") (pinfunction "G_1") (pintype "passive"))
    )
    (net (code "31") (name "N$49") (class "Default")
      (node (ref "IC3") (pin "14") (pinfunction "X_14") (pintype "bidirectional"))
      (node (ref "JUMPER") (pin "4") (pinfunction "4_4") (pintype "passive"))
      (node (ref "R30") (pin "2") (pinfunction "2_2") (pintype "passive"))
      (node (ref "SJ5") (pin "2") (pinfunction "2_2") (pintype "passive"))
    )
    (net (code "32") (name "N$50") (class "Default")
      (node (ref "IC3") (pin "15") (pinfunction "Y_15") (pintype "bidirectional"))
      (node (ref "R28") (pin "2") (pinfunction "2_2") (pintype "passive"))
      (node (ref "SJ4") (pin "2") (pinfunction "2_2") (pintype "passive"))
    )
    (net (code "33") (name "Net-(C1-Pad+)") (class "Default")
      (node (ref "C1") (pin "+") (pinfunction "+_+") (pintype "passive"))
      (node (ref "R1") (pin "1") (pinfunction "1_1") (pintype "passive"))
      (node (ref "R4") (pin "2") (pinfunction "2_2") (pintype "passive"))
    )
    (net (code "34") (name "Net-(C2-Pad2)") (class "Default")
      (node (ref "C2") (pin "2") (pinfunction "2_2") (pintype "passive"))
      (node (ref "R6") (pin "1") (pinfunction "1_1") (pintype "passive"))
    )
    (net (code "35") (name "Net-(C3-Pad2)") (class "Default")
      (node (ref "C3") (pin "2") (pinfunction "2_2") (pintype "passive"))
      (node (ref "R7") (pin "1") (pinfunction "1_1") (pintype "passive"))
    )
    (net (code "36") (name "Net-(C4-Pad2)") (class "Default")
      (node (ref "C4") (pin "2") (pinfunction "2_2") (pintype "passive"))
      (node (ref "R10") (pin "1") (pinfunction "1_1") (pintype "passive"))
    )
    (net (code "37") (name "Net-(C5-Pad2)") (class "Default")
      (node (ref "C5") (pin "2") (pinfunction "2_2") (pintype "passive"))
      (node (ref "R11") (pin "1") (pinfunction "1_1") (pintype "passive"))
      (node (ref "R8") (pin "2") (pinfunction "2_2") (pintype "passive"))
    )
    (net (code "38") (name "Net-(C6-Pad2)") (class "Default")
      (node (ref "C6") (pin "2") (pinfunction "2_2") (pintype "passive"))
      (node (ref "R8") (pin "1") (pinfunction "1_1") (pintype "passive"))
    )
    (net (code "39") (name "Net-(C11-Pad1)") (class "Default")
      (node (ref "C11") (pin "1") (pinfunction "1_1") (pintype "passive"))
      (node (ref "R16") (pin "2") (pinfunction "2_2") (pintype "passive"))
      (node (ref "R18") (pin "1") (pinfunction "1_1") (pintype "passive"))
    )
    (net (code "40") (name "Net-(C12-Pad1)") (class "Default")
      (node (ref "C12") (pin "1") (pinfunction "1_1") (pintype "passive"))
      (node (ref "R19") (pin "1") (pinfunction "1_1") (pintype "passive"))
    )
    (net (code "41") (name "Net-(C12-Pad2)") (class "Default")
      (node (ref "C12") (pin "2") (pinfunction "2_2") (pintype "passive"))
      (node (ref "D1") (pin "C") (pinfunction "C_C") (pintype "passive"))
      (node (ref "D2") (pin "A") (pinfunction "A_A") (pintype "passive"))
    )
    (net (code "42") (name "Net-(C13-Pad1)") (class "Default")
      (node (ref "C13") (pin "1") (pinfunction "1_1") (pintype "passive"))
      (node (ref "R17") (pin "2") (pinfunction "2_2") (pintype "passive"))
      (node (ref "R19") (pin "2") (pinfunction "2_2") (pintype "passive"))
    )
    (net (code "43") (name "Net-(C17-Pad1)") (class "Default")
      (node (ref "C17") (pin "1") (pinfunction "1_1") (pintype "passive"))
      (node (ref "D3") (pin "C") (pinfunction "C_C") (pintype "passive"))
      (node (ref "R27") (pin "2") (pinfunction "2_2") (pintype "passive"))
    )
    (net (code "44") (name "Net-(C20-Pad2)") (class "Default")
      (node (ref "C20") (pin "2") (pinfunction "2_2") (pintype "passive"))
      (node (ref "R34") (pin "1") (pinfunction "1_1") (pintype "passive"))
    )
    (net (code "45") (name "Net-(C21-Pad2)") (class "Default")
      (node (ref "C21") (pin "2") (pinfunction "2_2") (pintype "passive"))
      (node (ref "R35") (pin "1") (pinfunction "1_1") (pintype "passive"))
    )
    (net (code "46") (name "Net-(C54-Pad-)") (class "Default")
      (node (ref "C54") (pin "-") (pinfunction "-_-") (pintype "passive"))
      (node (ref "C55") (pin "2") (pinfunction "2_2") (pintype "passive"))
      (node (ref "D15") (pin "A") (pinfunction "A_A") (pintype "passive"))
      (node (ref "D19") (pin "A") (pinfunction "A_A") (pintype "passive"))
      (node (ref "SJ1") (pin "2") (pinfunction "2_2") (pintype "passive"))
      (node (ref "SJ7") (pin "1") (pinfunction "1_1") (pintype "passive"))
    )
    (net (code "47") (name "Net-(C63-Pad1)") (class "Default")
      (node (ref "C63") (pin "1") (pinfunction "1_1") (pintype "passive"))
      (node (ref "C65") (pin "+") (pinfunction "+_+") (pintype "passive"))
      (node (ref "L10") (pin "2") (pinfunction "2_2") (pintype "passive"))
      (node (ref "R52") (pin "2") (pinfunction "2_2") (pintype "passive"))
    )
    (net (code "48") (name "Net-(C64-Pad2)") (class "Default")
      (node (ref "C64") (pin "2") (pinfunction "2_2") (pintype "passive"))
      (node (ref "L11") (pin "2") (pinfunction "2_2") (pintype "passive"))
      (node (ref "L12") (pin "1") (pinfunction "1_1") (pintype "passive"))
      (node (ref "R53") (pin "1") (pinfunction "1_1") (pintype "passive"))
    )
    (net (code "49") (name "Net-(C66-Pad+)") (class "Default")
      (node (ref "C66") (pin "+") (pinfunction "+_+") (pintype "passive"))
      (node (ref "C70") (pin "2") (pinfunction "2_2") (pintype "passive"))
      (node (ref "L12") (pin "2") (pinfunction "2_2") (pintype "passive"))
    )
    (net (code "50") (name "Net-(C68-Pad1)") (class "Default")
      (node (ref "C68") (pin "1") (pinfunction "1_1") (pintype "passive"))
      (node (ref "SJ4") (pin "1") (pinfunction "1_1") (pintype "passive"))
    )
    (net (code "51") (name "Net-(C69-Pad1)") (class "Default")
      (node (ref "C69") (pin "1") (pinfunction "1_1") (pintype "passive"))
      (node (ref "SJ5") (pin "1") (pinfunction "1_1") (pintype "passive"))
    )
    (net (code "52") (name "Net-(C71-Pad1)") (class "Default")
      (node (ref "C71") (pin "1") (pinfunction "1_1") (pintype "passive"))
      (node (ref "R55") (pin "2") (pinfunction "2_2") (pintype "passive"))
      (node (ref "SD2") (pin "HACK") (pinfunction "HACK_HACK") (pintype "bidirectional"))
    )
    (net (code "53") (name "Net-(D3-PadA)") (class "Default")
      (node (ref "D3") (pin "A") (pinfunction "A_A") (pintype "passive"))
      (node (ref "R26") (pin "2") (pinfunction "2_2") (pintype "passive"))
    )
    (net (code "54") (name "Net-(D12-A)") (class "Default")
      (node (ref "D12") (pin "2") (pinfunction "A_2") (pintype "passive"))
      (node (ref "RJ2") (pin "8") (pinfunction "8_8") (pintype "passive"))
    )
    (net (code "55") (name "Net-(D13-A)") (class "Default")
      (node (ref "D13") (pin "2") (pinfunction "A_2") (pintype "passive"))
      (node (ref "DSUB1") (pin "8") (pinfunction "M_8") (pintype "passive"))
    )
    (net (code "56") (name "Net-(D14-C)") (class "Default")
      (node (ref "D14") (pin "1") (pinfunction "C_1") (pintype "passive"))
      (node (ref "JP1") (pin "1") (pinfunction "1_1") (pintype "passive"))
      (node (ref "L9") (pin "1") (pinfunction "1_1") (pintype "passive"))
    )
    (net (code "57") (name "Net-(D16-PadC)") (class "Default")
      (node (ref "D16") (pin "C") (pinfunction "C_C") (pintype "passive"))
      (node (ref "D17") (pin "A") (pinfunction "A_A") (pintype "passive"))
    )
    (net (code "58") (name "Net-(D18-PadA)") (class "Default")
      (node (ref "D18") (pin "A") (pinfunction "A_A") (pintype "passive"))
      (node (ref "D19") (pin "C") (pinfunction "C_C") (pintype "passive"))
      (node (ref "R55") (pin "1") (pinfunction "1_1") (pintype "passive"))
    )
    (net (code "59") (name "Net-(F2-Pad2)") (class "Default")
      (node (ref "F2") (pin "2") (pinfunction "2_2") (pintype "passive"))
      (node (ref "L7") (pin "1") (pinfunction "1_1") (pintype "passive"))
    )
    (net (code "60") (name "Net-(F_LED-Pad2)") (class "Default")
      (node (ref "F_LED") (pin "2") (pinfunction "2_2") (pintype "passive"))
      (node (ref "R27") (pin "1") (pinfunction "1_1") (pintype "passive"))
    )
    (net (code "61") (name "Net-(GAIN-PadE)") (class "Default")
      (node (ref "GAIN") (pin "E") (pinfunction "E_E") (pintype "passive"))
      (node (ref "R46") (pin "1") (pinfunction "1_1") (pintype "passive"))
    )
    (net (code "62") (name "Net-(HP_KIB-S)") (class "Default")
      (node (ref "C66") (pin "-") (pinfunction "-_-") (pintype "passive"))
      (node (ref "HP_KI") (pin "2") (pinfunction "S_2") (pintype "passive"))
      (node (ref "R56") (pin "1") (pinfunction "1_1") (pintype "passive"))
    )
    (net (code "63") (name "Net-(IC1A-+IN)") (class "Default")
      (node (ref "C10") (pin "1") (pinfunction "1_1") (pintype "passive"))
      (node (ref "IC1") (pin "3") (pinfunction "+IN_3") (pintype "input"))
      (node (ref "R10") (pin "2") (pinfunction "2_2") (pintype "passive"))
      (node (ref "R14") (pin "2") (pinfunction "2_2") (pintype "passive"))
    )
    (net (code "64") (name "Net-(IC1A--IN)") (class "Default")
      (node (ref "C6") (pin "1") (pinfunction "1_1") (pintype "passive"))
      (node (ref "C8") (pin "2") (pinfunction "2_2") (pintype "passive"))
      (node (ref "IC1") (pin "2") (pinfunction "-IN_2") (pintype "input"))
      (node (ref "R11") (pin "2") (pinfunction "2_2") (pintype "passive"))
      (node (ref "R12") (pin "1") (pinfunction "1_1") (pintype "passive"))
    )
    (net (code "65") (name "Net-(IC1B-+IN)") (class "Default")
      (node (ref "FENYELL") (pin "2") (pinfunction "2_2") (pintype "passive"))
      (node (ref "IC1") (pin "5") (pinfunction "+IN_5") (pintype "input"))
      (node (ref "Q1") (pin "3") (pinfunction "D_3") (pintype "passive"))
      (node (ref "R18") (pin "2") (pinfunction "2_2") (pintype "passive"))
    )
    (net (code "66") (name "Net-(IC1B--IN)") (class "Default")
      (node (ref "C14") (pin "2") (pinfunction "2_2") (pintype "passive"))
      (node (ref "IC1") (pin "6") (pinfunction "-IN_6") (pintype "input"))
      (node (ref "R20") (pin "2") (pinfunction "2_2") (pintype "passive"))
      (node (ref "R21") (pin "1") (pinfunction "1_1") (pintype "passive"))
    )
    (net (code "67") (name "Net-(IC1B-OUT)") (class "Default")
      (node (ref "C14") (pin "1") (pinfunction "1_1") (pintype "passive"))
      (node (ref "C15") (pin "2") (pinfunction "2_2") (pintype "passive"))
      (node (ref "IC1") (pin "7") (pinfunction "OUT_7") (pintype "output"))
      (node (ref "IC2") (pin "3") (pinfunction "+IN_3") (pintype "input"))
      (node (ref "R21") (pin "2") (pinfunction "2_2") (pintype "passive"))
    )
    (net (code "68") (name "Net-(IC2A--IN)") (class "Default")
      (node (ref "C16") (pin "2") (pinfunction "2_2") (pintype "passive"))
      (node (ref "IC2") (pin "2") (pinfunction "-IN_2") (pintype "input"))
      (node (ref "R22") (pin "2") (pinfunction "2_2") (pintype "passive"))
      (node (ref "R23") (pin "1") (pinfunction "1_1") (pintype "passive"))
    )
    (net (code "69") (name "Net-(IC2A-OUT)") (class "Default")
      (node (ref "C16") (pin "1") (pinfunction "1_1") (pintype "passive"))
      (node (ref "IC2") (pin "1") (pinfunction "OUT_1") (pintype "output"))
      (node (ref "LED1") (pin "K") (pinfunction "C_K") (pintype "passive"))
      (node (ref "R25") (pin "2") (pinfunction "2_2") (pintype "passive"))
      (node (ref "R26") (pin "1") (pinfunction "1_1") (pintype "passive"))
    )
    (net (code "70") (name "Net-(IC2B-+IN)") (class "Default")
      (node (ref "C7") (pin "1") (pinfunction "1_1") (pintype "passive"))
      (node (ref "IC2") (pin "5") (pinfunction "+IN_5") (pintype "input"))
      (node (ref "R6") (pin "2") (pinfunction "2_2") (pintype "passive"))
      (node (ref "R9") (pin "2") (pinfunction "2_2") (pintype "passive"))
    )
    (net (code "71") (name "Net-(IC2B--IN)") (class "Default")
      (node (ref "C9") (pin "2") (pinfunction "2_2") (pintype "passive"))
      (node (ref "IC2") (pin "6") (pinfunction "-IN_6") (pintype "input"))
      (node (ref "R13") (pin "1") (pinfunction "1_1") (pintype "passive"))
      (node (ref "R7") (pin "2") (pinfunction "2_2") (pintype "passive"))
    )
    (net (code "72") (name "Net-(IC2B-OUT)") (class "Default")
      (node (ref "C9") (pin "1") (pinfunction "1_1") (pintype "passive"))
      (node (ref "IC2") (pin "7") (pinfunction "OUT_7") (pintype "output"))
      (node (ref "R13") (pin "2") (pinfunction "2_2") (pintype "passive"))
      (node (ref "R17") (pin "1") (pinfunction "1_1") (pintype "passive"))
    )
    (net (code "73") (name "Net-(IC3A-Y0)") (class "Default")
      (node (ref "IC3") (pin "2") (pinfunction "Y0_2") (pintype "bidirectional"))
      (node (ref "IC3") (pin "4") (pinfunction "Z_4") (pintype "bidirectional"))
    )
    (net (code "74") (name "Net-(IC4A-+IN)") (class "Default")
      (node (ref "C15") (pin "1") (pinfunction "1_1") (pintype "passive"))
      (node (ref "IC4") (pin "3") (pinfunction "+IN_3") (pintype "input"))
      (node (ref "R24") (pin "2") (pinfunction "2_2") (pintype "passive"))
      (node (ref "R29") (pin "2") (pinfunction "2_2") (pintype "passive"))
    )
    (net (code "75") (name "Net-(IC4A--IN)") (class "Default")
      (node (ref "C18") (pin "2") (pinfunction "2_2") (pintype "passive"))
      (node (ref "IC4") (pin "2") (pinfunction "-IN_2") (pintype "input"))
      (node (ref "R31") (pin "2") (pinfunction "2_2") (pintype "passive"))
      (node (ref "R32") (pin "1") (pinfunction "1_1") (pintype "passive"))
    )
    (net (code "76") (name "Net-(IC4A-OUT)") (class "Default")
      (node (ref "C18") (pin "1") (pinfunction "1_1") (pintype "passive"))
      (node (ref "C20") (pin "1") (pinfunction "1_1") (pintype "passive"))
      (node (ref "IC4") (pin "1") (pinfunction "OUT_1") (pintype "output"))
      (node (ref "R32") (pin "2") (pinfunction "2_2") (pintype "passive"))
    )
    (net (code "77") (name "Net-(IC4B--IN)") (class "Default")
      (node (ref "C19") (pin "2") (pinfunction "2_2") (pintype "passive"))
      (node (ref "IC4") (pin "6") (pinfunction "-IN_6") (pintype "input"))
      (node (ref "R29") (pin "1") (pinfunction "1_1") (pintype "passive"))
      (node (ref "R33") (pin "1") (pinfunction "1_1") (pintype "passive"))
    )
    (net (code "78") (name "Net-(IC4B-OUT)") (class "Default")
      (node (ref "C19") (pin "1") (pinfunction "1_1") (pintype "passive"))
      (node (ref "C21") (pin "1") (pinfunction "1_1") (pintype "passive"))
      (node (ref "IC4") (pin "7") (pinfunction "OUT_7") (pintype "output"))
      (node (ref "R33") (pin "2") (pinfunction "2_2") (pintype "passive"))
    )
    (net (code "79") (name "Net-(IC11-BSL)") (class "Default")
      (node (ref "C61") (pin "1") (pinfunction "1_1") (pintype "passive"))
      (node (ref "IC11") (pin "21") (pinfunction "BSL_21") (pintype "passive"))
    )
    (net (code "80") (name "Net-(IC11-BSR)") (class "Default")
      (node (ref "C60") (pin "1") (pinfunction "1_1") (pintype "passive"))
      (node (ref "IC11") (pin "16") (pinfunction "BSR_16") (pintype "passive"))
    )
    (net (code "81") (name "Net-(IC11-BYPASS)") (class "Default")
      (node (ref "C56") (pin "1") (pinfunction "1_1") (pintype "passive"))
      (node (ref "IC11") (pin "7") (pinfunction "BYPASS_7") (pintype "input"))
    )
    (net (code "82") (name "Net-(IC11-GAIN0)") (class "Default")
      (node (ref "IC11") (pin "18") (pinfunction "GAIN0_18") (pintype "input"))
      (node (ref "SJ2") (pin "2") (pinfunction "2_2") (pintype "passive"))
    )
    (net (code "83") (name "Net-(IC11-LIN)") (class "Default")
      (node (ref "C69") (pin "2") (pinfunction "2_2") (pintype "passive"))
      (node (ref "IC11") (pin "5") (pinfunction "LIN_5") (pintype "input"))
    )
    (net (code "84") (name "Net-(IC11-MUTE)") (class "Default")
      (node (ref "IC11") (pin "4") (pinfunction "MUTE_4") (pintype "input"))
      (node (ref "Q3") (pin "3") (pinfunction "D_3") (pintype "passive"))
      (node (ref "R54") (pin "1") (pinfunction "1_1") (pintype "passive"))
    )
    (net (code "85") (name "Net-(IC11-RIN)") (class "Default")
      (node (ref "C68") (pin "2") (pinfunction "2_2") (pintype "passive"))
      (node (ref "IC11") (pin "6") (pinfunction "RIN_6") (pintype "input"))
    )
    (net (code "86") (name "Net-(IC11-VCLAMP)") (class "Default")
      (node (ref "C59") (pin "1") (pinfunction "1_1") (pintype "passive"))
      (node (ref "IC11") (pin "11") (pinfunction "VCLAMP_11") (pintype "input"))
    )
    (net (code "87") (name "Net-(J2A-S)") (class "Default")
      (node (ref "EXT1") (pin "E") (pinfunction "E_E") (pintype "passive"))
      (node (ref "J2") (pin "1") (pinfunction "S_1") (pintype "passive"))
    )
    (net (code "88") (name "Net-(J2B-S)") (class "Default")
      (node (ref "EXT1") (pin "S") (pinfunction "S_S") (pintype "passive"))
      (node (ref "J2") (pin "2") (pinfunction "S_2") (pintype "passive"))
    )
    (net (code "89") (name "Net-(J2C-S)") (class "Default")
      (node (ref "EXT1") (pin "A") (pinfunction "A_A") (pintype "passive"))
      (node (ref "J2") (pin "3") (pinfunction "S_3") (pintype "passive"))
    )
    (net (code "90") (name "Net-(J3A-S)") (class "Default")
      (node (ref "EXT2") (pin "E") (pinfunction "E_E") (pintype "passive"))
      (node (ref "J3") (pin "1") (pinfunction "S_1") (pintype "passive"))
    )
    (net (code "91") (name "Net-(J3B-S)") (class "Default")
      (node (ref "EXT2") (pin "S") (pinfunction "S_S") (pintype "passive"))
      (node (ref "J3") (pin "2") (pinfunction "S_2") (pintype "passive"))
    )
    (net (code "92") (name "Net-(J3C-S)") (class "Default")
      (node (ref "EXT2") (pin "A") (pinfunction "A_A") (pintype "passive"))
      (node (ref "J3") (pin "3") (pinfunction "S_3") (pintype "passive"))
    )
    (net (code "93") (name "Net-(LAMPAB-S)") (class "Default")
      (node (ref "LAMPA") (pin "2") (pinfunction "S_2") (pintype "passive"))
      (node (ref "T2") (pin "2") (pinfunction "C_2") (pintype "passive"))
    )
    (net (code "94") (name "Net-(LED1-PadA)") (class "Default")
      (node (ref "LED1") (pin "A") (pinfunction "A_A") (pintype "passive"))
      (node (ref "R23") (pin "2") (pinfunction "2_2") (pintype "passive"))
      (node (ref "R25") (pin "1") (pinfunction "1_1") (pintype "passive"))
    )
    (net (code "95") (name "Net-(PROG-Pad4)") (class "Default")
      (node (ref "PROG") (pin "4") (pinfunction "4_4") (pintype "passive"))
      (node (ref "R36") (pin "2") (pinfunction "2_2") (pintype "passive"))
    )
    (net (code "96") (name "Net-(PROG-Pad8)") (class "Default")
      (node (ref "PROG") (pin "8") (pinfunction "8_8") (pintype "passive"))
      (node (ref "R37") (pin "2") (pinfunction "2_2") (pintype "passive"))
    )
    (net (code "97") (name "Net-(SD2-CTRL)") (class "Default")
      (node (ref "C48") (pin "1") (pinfunction "1_1") (pintype "passive"))
      (node (ref "C49") (pin "+") (pinfunction "+_+") (pintype "passive"))
      (node (ref "R47") (pin "2") (pinfunction "2_2") (pintype "passive"))
      (node (ref "SD2") (pin "CONTROL") (pinfunction "CTRL_CONTROL") (pintype "bidirectional"))
    )
    (net (code "98") (name "Net-(SD2-IN+)") (class "Default")
      (node (ref "C22") (pin "+") (pinfunction "+_+") (pintype "passive"))
      (node (ref "C47") (pin "+") (pinfunction "+_+") (pintype "passive"))
      (node (ref "L7") (pin "2") (pinfunction "2_2") (pintype "passive"))
      (node (ref "SD2") (pin "INPUT+") (pinfunction "IN+_INPUT+") (pintype "bidirectional"))
    )
    (net (code "99") (name "Net-(SD2-IN-)") (class "Default")
      (node (ref "C22") (pin "-") (pinfunction "-_-") (pintype "passive"))
      (node (ref "C47") (pin "-") (pinfunction "-_-") (pintype "passive"))
      (node (ref "C48") (pin "2") (pinfunction "2_2") (pintype "passive"))
      (node (ref "C49") (pin "-") (pinfunction "-_-") (pintype "passive"))
      (node (ref "L8") (pin "2") (pinfunction "2_2") (pintype "passive"))
      (node (ref "R47") (pin "1") (pinfunction "1_1") (pintype "passive"))
      (node (ref "SD2") (pin "INPUT-") (pinfunction "IN-_INPUT-") (pintype "bidirectional"))
    )
    (net (code "100") (name "Net-(SD2-PadOUT-)") (class "Default")
      (node (ref "SD2") (pin "OUT-") (pinfunction "OUT-_OUT-") (pintype "bidirectional"))
      (node (ref "SJ7") (pin "2") (pinfunction "2_2") (pintype "passive"))
    )
    (net (code "101") (name "Net-(SP_KIB-S)") (class "Default")
      (node (ref "C65") (pin "-") (pinfunction "-_-") (pintype "passive"))
      (node (ref "SP_KI") (pin "2") (pinfunction "S_2") (pintype "passive"))
    )
    (net (code "102") (name "Net-(SV5-1)") (class "Default")
      (node (ref "LAMP") (pin "A") (pinfunction "A_A") (pintype "passive"))
      (node (ref "SV5") (pin "1A") (pinfunction "1_1A") (pintype "passive"))
    )
    (net (code "103") (name "Net-(SV5-2)") (class "Default")
      (node (ref "LAMP") (pin "S") (pinfunction "S_S") (pintype "passive"))
      (node (ref "SV5") (pin "1B") (pinfunction "2_1B") (pintype "passive"))
    )
    (net (code "104") (name "Net-(SV5-3)") (class "Default")
      (node (ref "LAMP") (pin "E") (pinfunction "E_E") (pintype "passive"))
      (node (ref "SV5") (pin "2A") (pinfunction "3_2A") (pintype "passive"))
    )
    (net (code "105") (name "Net-(SV5-5)") (class "Default")
      (node (ref "CRM") (pin "A") (pinfunction "A_A") (pintype "passive"))
      (node (ref "HP") (pin "A") (pinfunction "A_A") (pintype "passive"))
      (node (ref "SP") (pin "A") (pinfunction "A_A") (pintype "passive"))
      (node (ref "SV5") (pin "3A") (pinfunction "5_3A") (pintype "passive"))
      (node (ref "SV5") (pin "3B") (pinfunction "6_3B") (pintype "passive"))
    )
    (net (code "106") (name "Net-(SV5-7)") (class "Default")
      (node (ref "HP") (pin "E") (pinfunction "E_E") (pintype "passive"))
      (node (ref "SP") (pin "E") (pinfunction "E_E") (pintype "passive"))
      (node (ref "SV5") (pin "4A") (pinfunction "7_4A") (pintype "passive"))
      (node (ref "SV5") (pin "4B") (pinfunction "8_4B") (pintype "passive"))
    )
    (net (code "107") (name "Net-(SV5-10)") (class "Default")
      (node (ref "SP") (pin "S") (pinfunction "S_S") (pintype "passive"))
      (node (ref "SV5") (pin "5A") (pinfunction "9_5A") (pintype "passive"))
      (node (ref "SV5") (pin "5B") (pinfunction "10_5B") (pintype "passive"))
    )
    (net (code "108") (name "Net-(SV5-11)") (class "Default")
      (node (ref "HP") (pin "S") (pinfunction "S_S") (pintype "passive"))
      (node (ref "SV5") (pin "6A") (pinfunction "11_6A") (pintype "passive"))
      (node (ref "SV5") (pin "6B") (pinfunction "12_6B") (pintype "passive"))
    )
    (net (code "109") (name "Net-(SV5-13)") (class "Default")
      (node (ref "CRM") (pin "S") (pinfunction "S_S") (pintype "passive"))
      (node (ref "SV5") (pin "7A") (pinfunction "13_7A") (pintype "passive"))
    )
    (net (code "110") (name "Net-(SV5-14)") (class "Default")
      (node (ref "CRM") (pin "E") (pinfunction "E_E") (pintype "passive"))
      (node (ref "SV5") (pin "7B") (pinfunction "14_7B") (pintype "passive"))
    )
    (net (code "111") (name "Net-(SV5-15)") (class "Default")
      (node (ref "R46") (pin "2") (pinfunction "2_2") (pintype "passive"))
      (node (ref "SV5") (pin "8A") (pinfunction "15_8A") (pintype "passive"))
      (node (ref "SV5") (pin "8B") (pinfunction "16_8B") (pintype "passive"))
    )
    (net (code "112") (name "Net-(SV5-17)") (class "Default")
      (node (ref "GAIN") (pin "S") (pinfunction "S_S") (pintype "passive"))
      (node (ref "SV5") (pin "9A") (pinfunction "17_9A") (pintype "passive"))
      (node (ref "SV5") (pin "9B") (pinfunction "18_9B") (pintype "passive"))
    )
    (net (code "113") (name "Net-(SV5-19)") (class "Default")
      (node (ref "GAIN") (pin "A") (pinfunction "A_A") (pintype "passive"))
      (node (ref "SV5") (pin "10A") (pinfunction "19_10A") (pintype "passive"))
      (node (ref "SV5") (pin "10B") (pinfunction "20_10B") (pintype "passive"))
    )
    (net (code "114") (name "Net-(T2-E)") (class "Default")
      (node (ref "R50") (pin "1") (pinfunction "1_1") (pintype "passive"))
      (node (ref "T2") (pin "3") (pinfunction "E_3") (pintype "passive"))
    )
    (net (code "115") (name "OUT+") (class "Default")
      (node (ref "DSUB1") (pin "4") (pinfunction "M_4") (pintype "passive"))
      (node (ref "R34") (pin "2") (pinfunction "2_2") (pintype "passive"))
      (node (ref "RJ2") (pin "6") (pinfunction "6_6") (pintype "passive"))
    )
    (net (code "116") (name "OUT-") (class "Default")
      (node (ref "DSUB1") (pin "5") (pinfunction "M_5") (pintype "passive"))
      (node (ref "R35") (pin "2") (pinfunction "2_2") (pintype "passive"))
      (node (ref "RJ2") (pin "3") (pinfunction "3_3") (pintype "passive"))
    )
    (net (code "117") (name "POTI_JEL") (class "Default")
      (node (ref "C13") (pin "2") (pinfunction "2_2") (pintype "passive"))
      (node (ref "POTI") (pin "7") (pinfunction "7_7") (pintype "passive"))
      (node (ref "POTI") (pin "8") (pinfunction "8_8") (pintype "passive"))
    )
    (net (code "118") (name "SP") (class "Default")
      (node (ref "JUMPER") (pin "5") (pinfunction "5_5") (pintype "passive"))
      (node (ref "POTI") (pin "10") (pinfunction "10_10") (pintype "passive"))
      (node (ref "POTI") (pin "9") (pinfunction "9_9") (pintype "passive"))
    )
    (net (code "119") (name "SPM") (class "Default")
      (node (ref "DIGIT") (pin "5") (pinfunction "5_5") (pintype "passive"))
      (node (ref "DIGIT") (pin "6") (pinfunction "6_6") (pintype "passive"))
      (node (ref "IC3") (pin "10") (pinfunction "B_10") (pintype "input"))
    )
    (net (code "120") (name "SPOUT") (class "Default")
      (node (ref "C60") (pin "2") (pinfunction "2_2") (pintype "passive"))
      (node (ref "C71") (pin "2") (pinfunction "2_2") (pintype "passive"))
      (node (ref "IC11") (pin "15") (pinfunction "ROUT_15") (pintype "output"))
      (node (ref "L10") (pin "1") (pinfunction "1_1") (pintype "passive"))
    )
    (net (code "121") (name "VDD") (class "Default")
      (node (ref "C26") (pin "1") (pinfunction "1_1") (pintype "passive"))
      (node (ref "C57") (pin "+") (pinfunction "+_+") (pintype "passive"))
      (node (ref "C58") (pin "1") (pinfunction "1_1") (pintype "passive"))
      (node (ref "IC1") (pin "8") (pinfunction "V+_8") (pintype "power_in"))
      (node (ref "IC11") (pin "19") (pinfunction "AVCC_19") (pintype "input"))
      (node (ref "IC11") (pin "2") (pinfunction "~{SD}_2") (pintype "input"))
      (node (ref "IC11") (pin "20") (pinfunction "AVCC_20") (pintype "input"))
      (node (ref "IC2") (pin "8") (pinfunction "V+_8") (pintype "power_in"))
      (node (ref "IC4") (pin "8") (pinfunction "V+_8") (pintype "power_in"))
      (node (ref "R1") (pin "2") (pinfunction "2_2") (pintype "passive"))
      (node (ref "R51") (pin "1") (pinfunction "1_1") (pintype "passive"))
      (node (ref "SJ2") (pin "1") (pinfunction "1_1") (pintype "passive"))
    )
    (net (code "122") (name "VSS") (class "Default")
      (node (ref "C27") (pin "2") (pinfunction "2_2") (pintype "passive"))
      (node (ref "IC1") (pin "4") (pinfunction "V-_4") (pintype "power_in"))
      (node (ref "IC2") (pin "4") (pinfunction "V-_4") (pintype "power_in"))
      (node (ref "IC3") (pin "7") (pinfunction "VEE_7") (pintype "power_in"))
      (node (ref "IC4") (pin "4") (pinfunction "V-_4") (pintype "power_in"))
      (node (ref "SJ1") (pin "1") (pinfunction "1_1") (pintype "passive"))
    )
    (net (code "123") (name "X0") (class "Default")
      (node (ref "IC3") (pin "12") (pinfunction "X0_12") (pintype "bidirectional"))
      (node (ref "JUMPER") (pin "3") (pinfunction "3_3") (pintype "passive"))
    )
    (net (code "124") (name "unconnected-(IC12-GND-Pad2)") (class "Default")
      (node (ref "IC12") (pin "2") (pinfunction "GND_2") (pintype "passive"))
    )
    (net (code "125") (name "unconnected-(IC12-VI-Pad1)") (class "Default")
      (node (ref "IC12") (pin "1") (pinfunction "VI_1") (pintype "input"))
    )
    (net (code "126") (name "unconnected-(IC12-VO-Pad3)") (class "Default")
      (node (ref "IC12") (pin "3") (pinfunction "VO_3") (pintype "passive"))
    )
    (net (code "127") (name "unconnected-(JUMPER-Pad2)") (class "Default")
      (node (ref "JUMPER") (pin "2") (pinfunction "2_2") (pintype "passive"))
    )
    (net (code "128") (name "unconnected-(POTI-Pad4)") (class "Default")
      (node (ref "POTI") (pin "4") (pinfunction "4_4") (pintype "passive"))
    )
    (net (code "129") (name "unconnected-(PROG-Pad2)") (class "Default")
      (node (ref "PROG") (pin "2") (pinfunction "2_2") (pintype "passive"))
    )
    (net (code "130") (name "unconnected-(PROG-Pad10)") (class "Default")
      (node (ref "PROG") (pin "10") (pinfunction "10_10") (pintype "passive"))
    )
    (net (code "131") (name "unconnected-(SD2-PadSZAB)") (class "Default")
      (node (ref "SD2") (pin "SZAB") (pinfunction "SZAB_SZAB") (pintype "bidirectional"))
    )
    (net (code "132") (name "unconnected-(SV5-4-Pad2B)") (class "Default")
      (node (ref "SV5") (pin "2B") (pinfunction "4_2B") (pintype "passive"))
    )
    (net (code "133") (name "unconnected-(SV7-Pad1)") (class "Default")
      (node (ref "SV7") (pin "1") (pinfunction "1_1") (pintype "passive"))
    )
    (net (code "134") (name "unconnected-(SV7-Pad2)") (class "Default")
      (node (ref "SV7") (pin "2") (pinfunction "2_2") (pintype "passive"))
    )
    (net (code "135") (name "unconnected-(SV7-Pad3)") (class "Default")
      (node (ref "SV7") (pin "3") (pinfunction "3_3") (pintype "passive"))
    )
    (net (code "136") (name "unconnected-(SV7-Pad4)") (class "Default")
      (node (ref "SV7") (pin "4") (pinfunction "4_4") (pintype "passive"))
    )
    (net (code "137") (name "unconnected-(SV7-Pad5)") (class "Default")
      (node (ref "SV7") (pin "5") (pinfunction "5_5") (pintype "passive"))
    )
    (net (code "138") (name "unconnected-(SV7-Pad6)") (class "Default")
      (node (ref "SV7") (pin "6") (pinfunction "6_6") (pintype "passive"))
    )
    (net (code "139") (name "unconnected-(SV8-Pad1)") (class "Default")
      (node (ref "SV8") (pin "1") (pinfunction "1_1") (pintype "passive"))
    )
    (net (code "140") (name "unconnected-(SV8-Pad2)") (class "Default")
      (node (ref "SV8") (pin "2") (pinfunction "2_2") (pintype "passive"))
    )
    (net (code "141") (name "unconnected-(SV8-Pad3)") (class "Default")
      (node (ref "SV8") (pin "3") (pinfunction "3_3") (pintype "passive"))
    )
    (net (code "142") (name "unconnected-(SV8-Pad4)") (class "Default")
      (node (ref "SV8") (pin "4") (pinfunction "4_4") (pintype "passive"))
    )
    (net (code "143") (name "unconnected-(SV8-Pad5)") (class "Default")
      (node (ref "SV8") (pin "5") (pinfunction "5_5") (pintype "passive"))
    )
    (net (code "144") (name "unconnected-(SV8-Pad6)") (class "Default")
      (node (ref "SV8") (pin "6") (pinfunction "6_6") (pintype "passive"))
    )
    (net (code "145") (name "unconnected-(SV9-Pad1)") (class "Default")
      (node (ref "SV9") (pin "1") (pinfunction "1_1") (pintype "passive"))
    )
    (net (code "146") (name "unconnected-(SV9-Pad2)") (class "Default")
      (node (ref "SV9") (pin "2") (pinfunction "2_2") (pintype "passive"))
    )
    (net (code "147") (name "unconnected-(SV9-Pad3)") (class "Default")
      (node (ref "SV9") (pin "3") (pinfunction "3_3") (pintype "passive"))
    )
    (net (code "148") (name "unconnected-(SV9-Pad4)") (class "Default")
      (node (ref "SV9") (pin "4") (pinfunction "4_4") (pintype "passive"))
    )
    (net (code "149") (name "unconnected-(SV9-Pad5)") (class "Default")
      (node (ref "SV9") (pin "5") (pinfunction "5_5") (pintype "passive"))
    )
    (net (code "150") (name "unconnected-(SV9-Pad6)") (class "Default")
      (node (ref "SV9") (pin "6") (pinfunction "6_6") (pintype "passive"))
    )
    (net (code "151") (name "~{MCLR}") (class "Default")
      (node (ref "PROG") (pin "5") (pinfunction "5_5") (pintype "passive"))
      (node (ref "TAP") (pin "1") (pinfunction "1_1") (pintype "passive"))
      (node (ref "TAP") (pin "2") (pinfunction "2_2") (pintype "passive"))
    )
  )
)
